# EQBasePCB_V_1_0.net
KiCad netlist of a schematic drawn in EAGLE
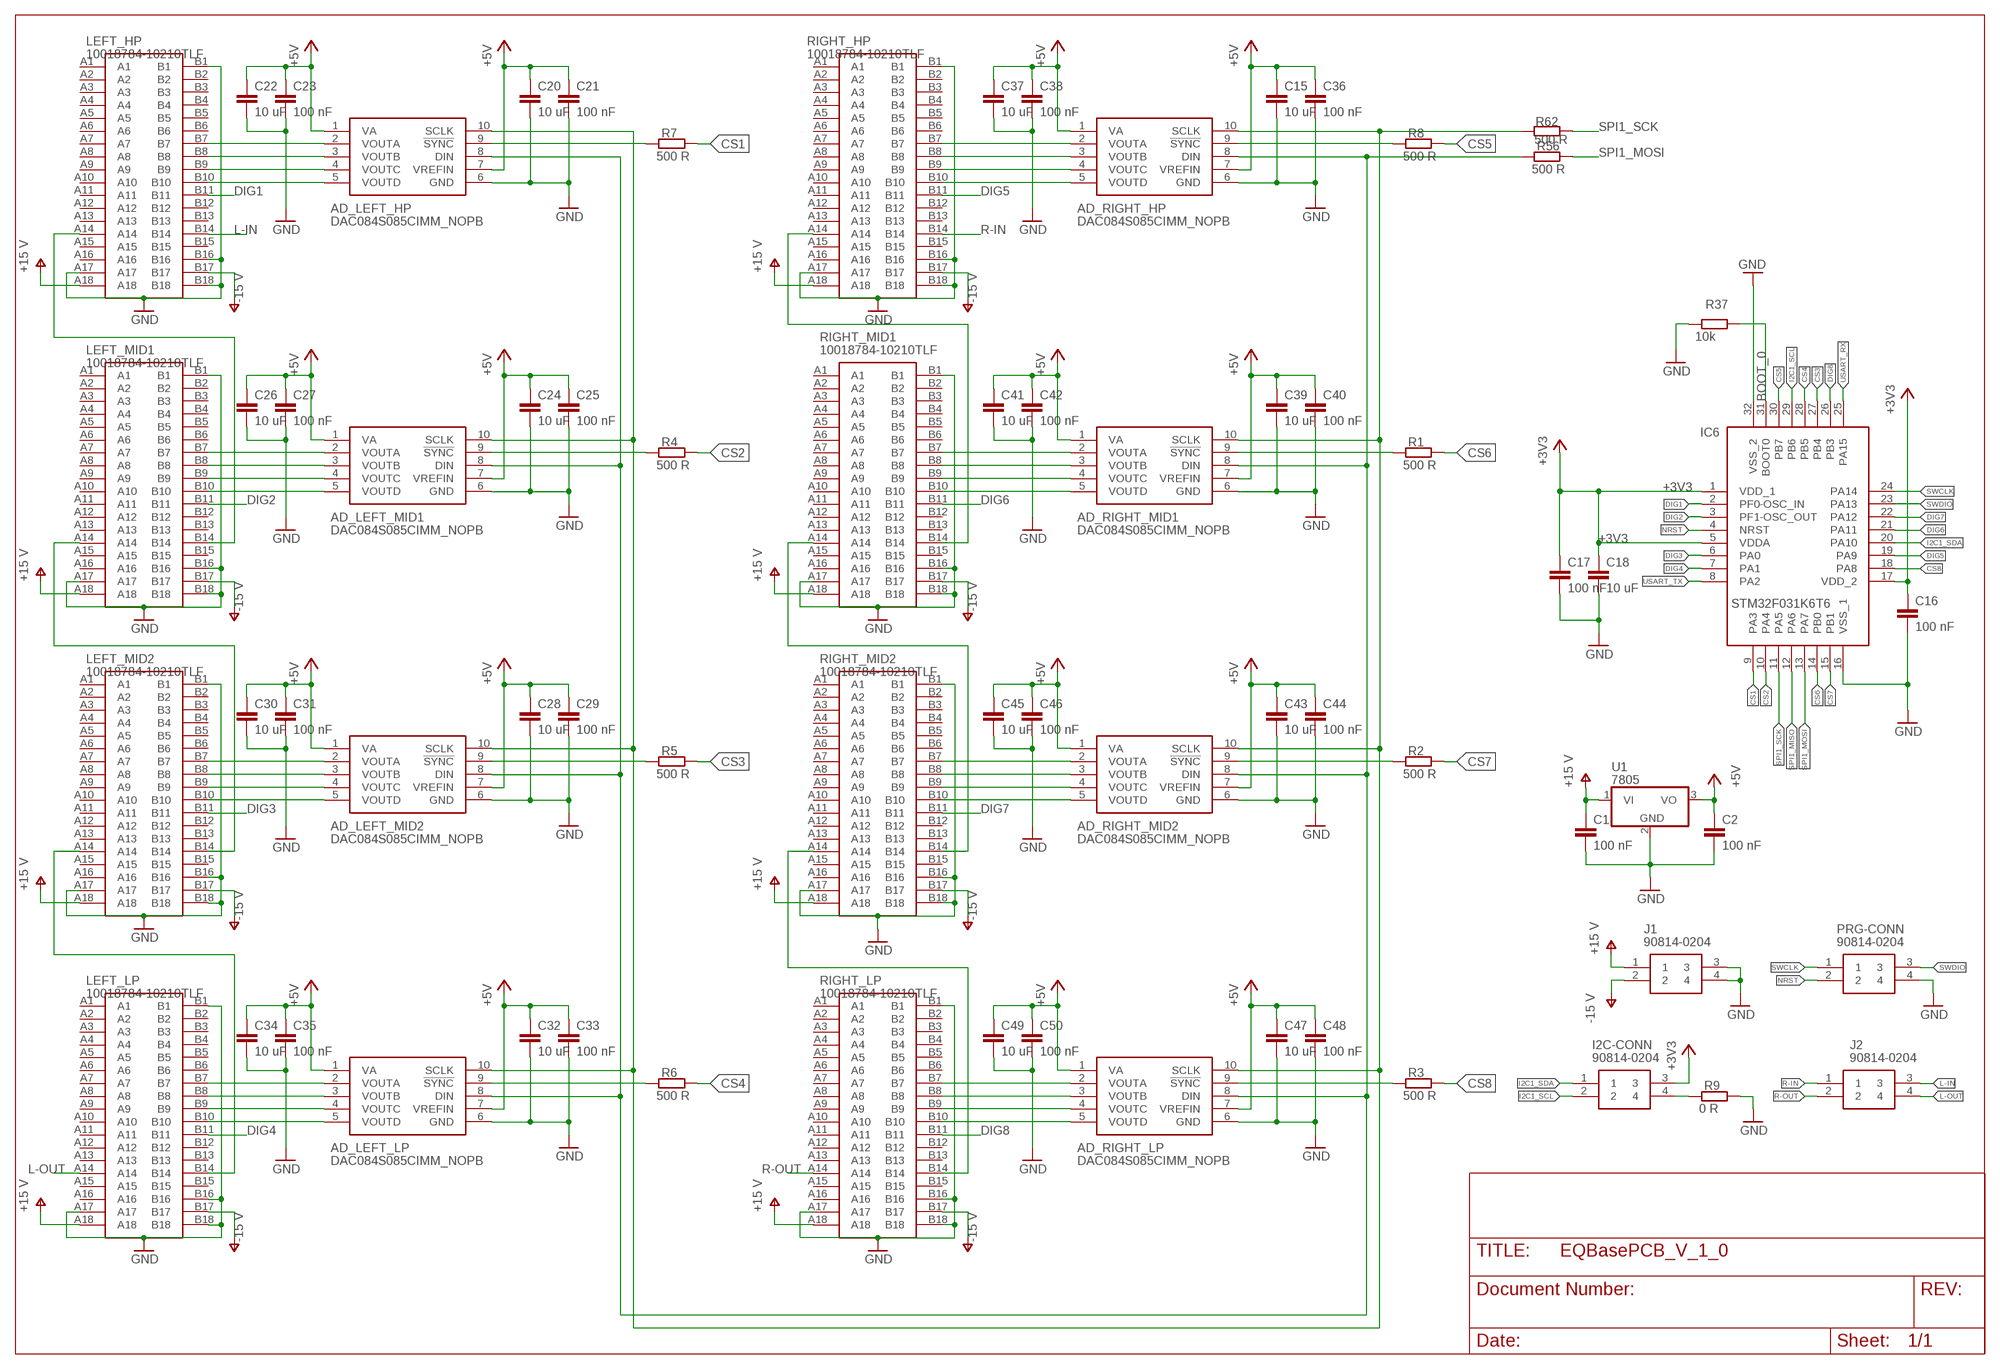
[diagram p0: schematic, sheet 1]

(export (version "E")
  (design (tool "Eeschema 10.0.6"))
  (components
    (comp (ref "AD_LEFT_HP")
      (value "DAC084S085CIMM_NOPB")
      (footprint "eagle-import:SOP50P490X110-10N")
      (fields (field (name "MOUSER_PART_NUMBER") "926-DAC084S085CIMMNO"))
      (libsource (lib "eagle-import") (part "DAC084S085CIMM_NOPB"))
    )
    (comp (ref "AD_LEFT_LP")
      (value "DAC084S085CIMM_NOPB")
      (footprint "eagle-import:SOP50P490X110-10N")
      (fields (field (name "MOUSER_PART_NUMBER") "926-DAC084S085CIMMNO"))
      (libsource (lib "eagle-import") (part "DAC084S085CIMM_NOPB"))
    )
    (comp (ref "AD_LEFT_MID1")
      (value "DAC084S085CIMM_NOPB")
      (footprint "eagle-import:SOP50P490X110-10N")
      (fields (field (name "MOUSER_PART_NUMBER") "926-DAC084S085CIMMNO"))
      (libsource (lib "eagle-import") (part "DAC084S085CIMM_NOPB"))
    )
    (comp (ref "AD_LEFT_MID2")
      (value "DAC084S085CIMM_NOPB")
      (footprint "eagle-import:SOP50P490X110-10N")
      (fields (field (name "MOUSER_PART_NUMBER") "926-DAC084S085CIMMNO"))
      (libsource (lib "eagle-import") (part "DAC084S085CIMM_NOPB"))
    )
    (comp (ref "AD_RIGHT_HP")
      (value "DAC084S085CIMM_NOPB")
      (footprint "eagle-import:SOP50P490X110-10N")
      (fields (field (name "MOUSER_PART_NUMBER") "926-DAC084S085CIMMNO"))
      (libsource (lib "eagle-import") (part "DAC084S085CIMM_NOPB"))
    )
    (comp (ref "AD_RIGHT_LP")
      (value "DAC084S085CIMM_NOPB")
      (footprint "eagle-import:SOP50P490X110-10N")
      (fields (field (name "MOUSER_PART_NUMBER") "926-DAC084S085CIMMNO"))
      (libsource (lib "eagle-import") (part "DAC084S085CIMM_NOPB"))
    )
    (comp (ref "AD_RIGHT_MID1")
      (value "DAC084S085CIMM_NOPB")
      (footprint "eagle-import:SOP50P490X110-10N")
      (fields (field (name "MOUSER_PART_NUMBER") "926-DAC084S085CIMMNO"))
      (libsource (lib "eagle-import") (part "DAC084S085CIMM_NOPB"))
    )
    (comp (ref "AD_RIGHT_MID2")
      (value "DAC084S085CIMM_NOPB")
      (footprint "eagle-import:SOP50P490X110-10N")
      (fields (field (name "MOUSER_PART_NUMBER") "926-DAC084S085CIMMNO"))
      (libsource (lib "eagle-import") (part "DAC084S085CIMM_NOPB"))
    )
    (comp (ref "C1")
      (value "100 nF")
      (footprint "eagle-import:C0603")
      (libsource (lib "eagle-import") (part "CAPACITOR_0603"))
    )
    (comp (ref "C2")
      (value "100 nF")
      (footprint "eagle-import:C0603")
      (libsource (lib "eagle-import") (part "CAPACITOR_0603"))
    )
    (comp (ref "C15")
      (value "10 uF")
      (footprint "eagle-import:C1206")
      (libsource (lib "eagle-import") (part "CAPACITOR_1206"))
    )
    (comp (ref "C16")
      (value "100 nF")
      (footprint "eagle-import:C0603")
      (libsource (lib "eagle-import") (part "CAPACITOR_0603"))
    )
    (comp (ref "C17")
      (value "100 nF")
      (footprint "eagle-import:C0603")
      (libsource (lib "eagle-import") (part "CAPACITOR_0603"))
    )
    (comp (ref "C18")
      (value "10 uF")
      (footprint "eagle-import:C1206")
      (libsource (lib "eagle-import") (part "CAPACITOR_1206"))
    )
    (comp (ref "C20")
      (value "10 uF")
      (footprint "eagle-import:C1206")
      (libsource (lib "eagle-import") (part "CAPACITOR_1206"))
    )
    (comp (ref "C21")
      (value "100 nF")
      (footprint "eagle-import:C0603")
      (libsource (lib "eagle-import") (part "CAPACITOR_0603"))
    )
    (comp (ref "C22")
      (value "10 uF")
      (footprint "eagle-import:C1206")
      (libsource (lib "eagle-import") (part "CAPACITOR_1206"))
    )
    (comp (ref "C23")
      (value "100 nF")
      (footprint "eagle-import:C0603")
      (libsource (lib "eagle-import") (part "CAPACITOR_0603"))
    )
    (comp (ref "C24")
      (value "10 uF")
      (footprint "eagle-import:C1206")
      (libsource (lib "eagle-import") (part "CAPACITOR_1206"))
    )
    (comp (ref "C25")
      (value "100 nF")
      (footprint "eagle-import:C0603")
      (libsource (lib "eagle-import") (part "CAPACITOR_0603"))
    )
    (comp (ref "C26")
      (value "10 uF")
      (footprint "eagle-import:C1206")
      (libsource (lib "eagle-import") (part "CAPACITOR_1206"))
    )
    (comp (ref "C27")
      (value "100 nF")
      (footprint "eagle-import:C0603")
      (libsource (lib "eagle-import") (part "CAPACITOR_0603"))
    )
    (comp (ref "C28")
      (value "10 uF")
      (footprint "eagle-import:C1206")
      (libsource (lib "eagle-import") (part "CAPACITOR_1206"))
    )
    (comp (ref "C29")
      (value "100 nF")
      (footprint "eagle-import:C0603")
      (libsource (lib "eagle-import") (part "CAPACITOR_0603"))
    )
    (comp (ref "C30")
      (value "10 uF")
      (footprint "eagle-import:C1206")
      (libsource (lib "eagle-import") (part "CAPACITOR_1206"))
    )
    (comp (ref "C31")
      (value "100 nF")
      (footprint "eagle-import:C0603")
      (libsource (lib "eagle-import") (part "CAPACITOR_0603"))
    )
    (comp (ref "C32")
      (value "10 uF")
      (footprint "eagle-import:C1206")
      (libsource (lib "eagle-import") (part "CAPACITOR_1206"))
    )
    (comp (ref "C33")
      (value "100 nF")
      (footprint "eagle-import:C0603")
      (libsource (lib "eagle-import") (part "CAPACITOR_0603"))
    )
    (comp (ref "C34")
      (value "10 uF")
      (footprint "eagle-import:C1206")
      (libsource (lib "eagle-import") (part "CAPACITOR_1206"))
    )
    (comp (ref "C35")
      (value "100 nF")
      (footprint "eagle-import:C0603")
      (libsource (lib "eagle-import") (part "CAPACITOR_0603"))
    )
    (comp (ref "C36")
      (value "100 nF")
      (footprint "eagle-import:C0603")
      (libsource (lib "eagle-import") (part "CAPACITOR_0603"))
    )
    (comp (ref "C37")
      (value "10 uF")
      (footprint "eagle-import:C1206")
      (libsource (lib "eagle-import") (part "CAPACITOR_1206"))
    )
    (comp (ref "C38")
      (value "100 nF")
      (footprint "eagle-import:C0603")
      (libsource (lib "eagle-import") (part "CAPACITOR_0603"))
    )
    (comp (ref "C39")
      (value "10 uF")
      (footprint "eagle-import:C1206")
      (libsource (lib "eagle-import") (part "CAPACITOR_1206"))
    )
    (comp (ref "C40")
      (value "100 nF")
      (footprint "eagle-import:C0603")
      (libsource (lib "eagle-import") (part "CAPACITOR_0603"))
    )
    (comp (ref "C41")
      (value "10 uF")
      (footprint "eagle-import:C1206")
      (libsource (lib "eagle-import") (part "CAPACITOR_1206"))
    )
    (comp (ref "C42")
      (value "100 nF")
      (footprint "eagle-import:C0603")
      (libsource (lib "eagle-import") (part "CAPACITOR_0603"))
    )
    (comp (ref "C43")
      (value "10 uF")
      (footprint "eagle-import:C1206")
      (libsource (lib "eagle-import") (part "CAPACITOR_1206"))
    )
    (comp (ref "C44")
      (value "100 nF")
      (footprint "eagle-import:C0603")
      (libsource (lib "eagle-import") (part "CAPACITOR_0603"))
    )
    (comp (ref "C45")
      (value "10 uF")
      (footprint "eagle-import:C1206")
      (libsource (lib "eagle-import") (part "CAPACITOR_1206"))
    )
    (comp (ref "C46")
      (value "100 nF")
      (footprint "eagle-import:C0603")
      (libsource (lib "eagle-import") (part "CAPACITOR_0603"))
    )
    (comp (ref "C47")
      (value "10 uF")
      (footprint "eagle-import:C1206")
      (libsource (lib "eagle-import") (part "CAPACITOR_1206"))
    )
    (comp (ref "C48")
      (value "100 nF")
      (footprint "eagle-import:C0603")
      (libsource (lib "eagle-import") (part "CAPACITOR_0603"))
    )
    (comp (ref "C49")
      (value "10 uF")
      (footprint "eagle-import:C1206")
      (libsource (lib "eagle-import") (part "CAPACITOR_1206"))
    )
    (comp (ref "C50")
      (value "100 nF")
      (footprint "eagle-import:C0603")
      (libsource (lib "eagle-import") (part "CAPACITOR_0603"))
    )
    (comp (ref "I2C-CONN")
      (value "90814-0204")
      (footprint "eagle-import:MOLEX_90814-0204")
      (fields (field (name "MOUSER_PART_NUMBER") "538-90814-0204"))
      (libsource (lib "eagle-import") (part "90814-0204"))
    )
    (comp (ref "IC6")
      (value "STM32F031K6T6")
      (footprint "eagle-import:QFP80P900X900X160-32N")
      (fields (field (name "MOUSER_PART_NUMBER") "511-STM32F031K6T6"))
      (libsource (lib "eagle-import") (part "STM32F031K6T6"))
    )
    (comp (ref "J1")
      (value "90814-0204")
      (footprint "eagle-import:MOLEX_90814-0204")
      (fields (field (name "MOUSER_PART_NUMBER") "538-90814-0204"))
      (libsource (lib "eagle-import") (part "90814-0204"))
    )
    (comp (ref "J2")
      (value "90814-0204")
      (footprint "eagle-import:MOLEX_90814-0204")
      (fields (field (name "MOUSER_PART_NUMBER") "538-90814-0204"))
      (libsource (lib "eagle-import") (part "90814-0204"))
    )
    (comp (ref "LEFT_HP")
      (value "10018784-10210TLF")
      (footprint "eagle-import:1001878410210TLF")
      (fields (field (name "MOUSER_PART_NUMBER") "649-1001878410210TLF"))
      (libsource (lib "eagle-import") (part "10018784-10210TLF"))
    )
    (comp (ref "LEFT_LP")
      (value "10018784-10210TLF")
      (footprint "eagle-import:1001878410210TLF")
      (fields (field (name "MOUSER_PART_NUMBER") "649-1001878410210TLF"))
      (libsource (lib "eagle-import") (part "10018784-10210TLF"))
    )
    (comp (ref "LEFT_MID1")
      (value "10018784-10210TLF")
      (footprint "eagle-import:1001878410210TLF")
      (fields (field (name "MOUSER_PART_NUMBER") "649-1001878410210TLF"))
      (libsource (lib "eagle-import") (part "10018784-10210TLF"))
    )
    (comp (ref "LEFT_MID2")
      (value "10018784-10210TLF")
      (footprint "eagle-import:1001878410210TLF")
      (fields (field (name "MOUSER_PART_NUMBER") "649-1001878410210TLF"))
      (libsource (lib "eagle-import") (part "10018784-10210TLF"))
    )
    (comp (ref "PRG-CONN")
      (value "90814-0204")
      (footprint "eagle-import:MOLEX_90814-0204")
      (fields (field (name "MOUSER_PART_NUMBER") "538-90814-0204"))
      (libsource (lib "eagle-import") (part "90814-0204"))
    )
    (comp (ref "R1")
      (value "500 R")
      (footprint "eagle-import:R0603")
      (libsource (lib "eagle-import") (part "RESISTOR_0603"))
    )
    (comp (ref "R2")
      (value "500 R")
      (footprint "eagle-import:R0603")
      (libsource (lib "eagle-import") (part "RESISTOR_0603"))
    )
    (comp (ref "R3")
      (value "500 R")
      (footprint "eagle-import:R0603")
      (libsource (lib "eagle-import") (part "RESISTOR_0603"))
    )
    (comp (ref "R4")
      (value "500 R")
      (footprint "eagle-import:R0603")
      (libsource (lib "eagle-import") (part "RESISTOR_0603"))
    )
    (comp (ref "R5")
      (value "500 R")
      (footprint "eagle-import:R0603")
      (libsource (lib "eagle-import") (part "RESISTOR_0603"))
    )
    (comp (ref "R6")
      (value "500 R")
      (footprint "eagle-import:R0603")
      (libsource (lib "eagle-import") (part "RESISTOR_0603"))
    )
    (comp (ref "R7")
      (value "500 R")
      (footprint "eagle-import:R0603")
      (libsource (lib "eagle-import") (part "RESISTOR_0603"))
    )
    (comp (ref "R8")
      (value "500 R")
      (footprint "eagle-import:R0603")
      (libsource (lib "eagle-import") (part "RESISTOR_0603"))
    )
    (comp (ref "R9")
      (value "0 R")
      (footprint "eagle-import:R0603")
      (libsource (lib "eagle-import") (part "RESISTOR_0603"))
    )
    (comp (ref "R37")
      (value "10k")
      (footprint "eagle-import:R0603")
      (libsource (lib "eagle-import") (part "RESISTOR_0603"))
    )
    (comp (ref "R56")
      (value "500 R")
      (footprint "eagle-import:R0603")
      (libsource (lib "eagle-import") (part "RESISTOR_0603"))
    )
    (comp (ref "R62")
      (value "500 R")
      (footprint "eagle-import:R0603")
      (libsource (lib "eagle-import") (part "RESISTOR_0603"))
    )
    (comp (ref "RIGHT_HP")
      (value "10018784-10210TLF")
      (footprint "eagle-import:1001878410210TLF")
      (fields (field (name "MOUSER_PART_NUMBER") "649-1001878410210TLF"))
      (libsource (lib "eagle-import") (part "10018784-10210TLF"))
    )
    (comp (ref "RIGHT_LP")
      (value "10018784-10210TLF")
      (footprint "eagle-import:1001878410210TLF")
      (fields (field (name "MOUSER_PART_NUMBER") "649-1001878410210TLF"))
      (libsource (lib "eagle-import") (part "10018784-10210TLF"))
    )
    (comp (ref "RIGHT_MID1")
      (value "10018784-10210TLF")
      (footprint "eagle-import:1001878410210TLF")
      (fields (field (name "MOUSER_PART_NUMBER") "649-1001878410210TLF"))
      (libsource (lib "eagle-import") (part "10018784-10210TLF"))
    )
    (comp (ref "RIGHT_MID2")
      (value "10018784-10210TLF")
      (footprint "eagle-import:1001878410210TLF")
      (fields (field (name "MOUSER_PART_NUMBER") "649-1001878410210TLF"))
      (libsource (lib "eagle-import") (part "10018784-10210TLF"))
    )
    (comp (ref "U1")
      (value "7805")
      (footprint "eagle-import:TO252")
      (libsource (lib "eagle-import") (part "78_SMD"))
    )
  )
  (nets
    (net (code "1") (name "+3V3") (class "Default")
      (node (ref "C16") (pin "1") (pinfunction "1_1") (pintype "passive"))
      (node (ref "C17") (pin "1") (pinfunction "1_1") (pintype "passive"))
      (node (ref "C18") (pin "1") (pinfunction "1_1") (pintype "passive"))
      (node (ref "I2C-CONN") (pin "3") (pinfunction "3_3") (pintype "bidirectional"))
      (node (ref "IC6") (pin "1") (pinfunction "VDD_1_1") (pintype "bidirectional"))
      (node (ref "IC6") (pin "17") (pinfunction "VDD_2_17") (pintype "bidirectional"))
      (node (ref "IC6") (pin "5") (pinfunction "VDDA_5") (pintype "bidirectional"))
    )
    (net (code "2") (name "+5V") (class "Default")
      (node (ref "AD_LEFT_HP") (pin "1") (pinfunction "VA_1") (pintype "bidirectional"))
      (node (ref "AD_LEFT_HP") (pin "7") (pinfunction "VREFIN_7") (pintype "bidirectional"))
      (node (ref "AD_LEFT_LP") (pin "1") (pinfunction "VA_1") (pintype "bidirectional"))
      (node (ref "AD_LEFT_LP") (pin "7") (pinfunction "VREFIN_7") (pintype "bidirectional"))
      (node (ref "AD_LEFT_MID1") (pin "1") (pinfunction "VA_1") (pintype "bidirectional"))
      (node (ref "AD_LEFT_MID1") (pin "7") (pinfunction "VREFIN_7") (pintype "bidirectional"))
      (node (ref "AD_LEFT_MID2") (pin "1") (pinfunction "VA_1") (pintype "bidirectional"))
      (node (ref "AD_LEFT_MID2") (pin "7") (pinfunction "VREFIN_7") (pintype "bidirectional"))
      (node (ref "AD_RIGHT_HP") (pin "1") (pinfunction "VA_1") (pintype "bidirectional"))
      (node (ref "AD_RIGHT_HP") (pin "7") (pinfunction "VREFIN_7") (pintype "bidirectional"))
      (node (ref "AD_RIGHT_LP") (pin "1") (pinfunction "VA_1") (pintype "bidirectional"))
      (node (ref "AD_RIGHT_LP") (pin "7") (pinfunction "VREFIN_7") (pintype "bidirectional"))
      (node (ref "AD_RIGHT_MID1") (pin "1") (pinfunction "VA_1") (pintype "bidirectional"))
      (node (ref "AD_RIGHT_MID1") (pin "7") (pinfunction "VREFIN_7") (pintype "bidirectional"))
      (node (ref "AD_RIGHT_MID2") (pin "1") (pinfunction "VA_1") (pintype "bidirectional"))
      (node (ref "AD_RIGHT_MID2") (pin "7") (pinfunction "VREFIN_7") (pintype "bidirectional"))
      (node (ref "C15") (pin "1") (pinfunction "1_1") (pintype "passive"))
      (node (ref "C2") (pin "1") (pinfunction "1_1") (pintype "passive"))
      (node (ref "C20") (pin "1") (pinfunction "1_1") (pintype "passive"))
      (node (ref "C21") (pin "1") (pinfunction "1_1") (pintype "passive"))
      (node (ref "C22") (pin "1") (pinfunction "1_1") (pintype "passive"))
      (node (ref "C23") (pin "1") (pinfunction "1_1") (pintype "passive"))
      (node (ref "C24") (pin "1") (pinfunction "1_1") (pintype "passive"))
      (node (ref "C25") (pin "1") (pinfunction "1_1") (pintype "passive"))
      (node (ref "C26") (pin "1") (pinfunction "1_1") (pintype "passive"))
      (node (ref "C27") (pin "1") (pinfunction "1_1") (pintype "passive"))
      (node (ref "C28") (pin "1") (pinfunction "1_1") (pintype "passive"))
      (node (ref "C29") (pin "1") (pinfunction "1_1") (pintype "passive"))
      (node (ref "C30") (pin "1") (pinfunction "1_1") (pintype "passive"))
      (node (ref "C31") (pin "1") (pinfunction "1_1") (pintype "passive"))
      (node (ref "C32") (pin "1") (pinfunction "1_1") (pintype "passive"))
      (node (ref "C33") (pin "1") (pinfunction "1_1") (pintype "passive"))
      (node (ref "C34") (pin "1") (pinfunction "1_1") (pintype "passive"))
      (node (ref "C35") (pin "1") (pinfunction "1_1") (pintype "passive"))
      (node (ref "C36") (pin "1") (pinfunction "1_1") (pintype "passive"))
      (node (ref "C37") (pin "1") (pinfunction "1_1") (pintype "passive"))
      (node (ref "C38") (pin "1") (pinfunction "1_1") (pintype "passive"))
      (node (ref "C39") (pin "1") (pinfunction "1_1") (pintype "passive"))
      (node (ref "C40") (pin "1") (pinfunction "1_1") (pintype "passive"))
      (node (ref "C41") (pin "1") (pinfunction "1_1") (pintype "passive"))
      (node (ref "C42") (pin "1") (pinfunction "1_1") (pintype "passive"))
      (node (ref "C43") (pin "1") (pinfunction "1_1") (pintype "passive"))
      (node (ref "C44") (pin "1") (pinfunction "1_1") (pintype "passive"))
      (node (ref "C45") (pin "1") (pinfunction "1_1") (pintype "passive"))
      (node (ref "C46") (pin "1") (pinfunction "1_1") (pintype "passive"))
      (node (ref "C47") (pin "1") (pinfunction "1_1") (pintype "passive"))
      (node (ref "C48") (pin "1") (pinfunction "1_1") (pintype "passive"))
      (node (ref "C49") (pin "1") (pinfunction "1_1") (pintype "passive"))
      (node (ref "C50") (pin "1") (pinfunction "1_1") (pintype "passive"))
      (node (ref "U1") (pin "3") (pinfunction "VO_3") (pintype "passive"))
    )
    (net (code "3") (name "+15 V") (class "Default")
      (node (ref "C1") (pin "1") (pinfunction "1_1") (pintype "passive"))
      (node (ref "J1") (pin "1") (pinfunction "1_1") (pintype "bidirectional"))
      (node (ref "LEFT_HP") (pin "A18") (pinfunction "A18_A18") (pintype "bidirectional"))
      (node (ref "LEFT_LP") (pin "A18") (pinfunction "A18_A18") (pintype "bidirectional"))
      (node (ref "LEFT_MID1") (pin "A18") (pinfunction "A18_A18") (pintype "bidirectional"))
      (node (ref "LEFT_MID2") (pin "A18") (pinfunction "A18_A18") (pintype "bidirectional"))
      (node (ref "RIGHT_HP") (pin "A18") (pinfunction "A18_A18") (pintype "bidirectional"))
      (node (ref "RIGHT_LP") (pin "A18") (pinfunction "A18_A18") (pintype "bidirectional"))
      (node (ref "RIGHT_MID1") (pin "A18") (pinfunction "A18_A18") (pintype "bidirectional"))
      (node (ref "RIGHT_MID2") (pin "A18") (pinfunction "A18_A18") (pintype "bidirectional"))
      (node (ref "U1") (pin "1") (pinfunction "VI_1") (pintype "input"))
    )
    (net (code "4") (name "-15 V") (class "Default")
      (node (ref "J1") (pin "2") (pinfunction "2_2") (pintype "bidirectional"))
      (node (ref "LEFT_HP") (pin "B17") (pinfunction "B17_B17") (pintype "bidirectional"))
      (node (ref "LEFT_LP") (pin "B17") (pinfunction "B17_B17") (pintype "bidirectional"))
      (node (ref "LEFT_MID1") (pin "B17") (pinfunction "B17_B17") (pintype "bidirectional"))
      (node (ref "LEFT_MID2") (pin "B17") (pinfunction "B17_B17") (pintype "bidirectional"))
      (node (ref "RIGHT_HP") (pin "B17") (pinfunction "B17_B17") (pintype "bidirectional"))
      (node (ref "RIGHT_LP") (pin "B17") (pinfunction "B17_B17") (pintype "bidirectional"))
      (node (ref "RIGHT_MID1") (pin "B17") (pinfunction "B17_B17") (pintype "bidirectional"))
      (node (ref "RIGHT_MID2") (pin "B17") (pinfunction "B17_B17") (pintype "bidirectional"))
    )
    (net (code "5") (name "/BOOT_0") (class "Default")
      (node (ref "IC6") (pin "31") (pinfunction "BOOT0_31") (pintype "bidirectional"))
      (node (ref "R37") (pin "2") (pinfunction "2_2") (pintype "passive"))
    )
    (net (code "6") (name "CS1") (class "Default")
      (node (ref "IC6") (pin "9") (pinfunction "PA3_9") (pintype "bidirectional"))
      (node (ref "R7") (pin "2") (pinfunction "2_2") (pintype "passive"))
    )
    (net (code "7") (name "CS2") (class "Default")
      (node (ref "IC6") (pin "10") (pinfunction "PA4_10") (pintype "bidirectional"))
      (node (ref "R4") (pin "2") (pinfunction "2_2") (pintype "passive"))
    )
    (net (code "8") (name "CS3") (class "Default")
      (node (ref "IC6") (pin "27") (pinfunction "PB4_27") (pintype "bidirectional"))
      (node (ref "R5") (pin "2") (pinfunction "2_2") (pintype "passive"))
    )
    (net (code "9") (name "CS4") (class "Default")
      (node (ref "IC6") (pin "28") (pinfunction "PB5_28") (pintype "bidirectional"))
      (node (ref "R6") (pin "2") (pinfunction "2_2") (pintype "passive"))
    )
    (net (code "10") (name "CS5") (class "Default")
      (node (ref "IC6") (pin "30") (pinfunction "PB7_30") (pintype "bidirectional"))
      (node (ref "R8") (pin "2") (pinfunction "2_2") (pintype "passive"))
    )
    (net (code "11") (name "CS6") (class "Default")
      (node (ref "IC6") (pin "14") (pinfunction "PB0_14") (pintype "bidirectional"))
      (node (ref "R1") (pin "2") (pinfunction "2_2") (pintype "passive"))
    )
    (net (code "12") (name "CS7") (class "Default")
      (node (ref "IC6") (pin "15") (pinfunction "PB1_15") (pintype "bidirectional"))
      (node (ref "R2") (pin "2") (pinfunction "2_2") (pintype "passive"))
    )
    (net (code "13") (name "CS8") (class "Default")
      (node (ref "IC6") (pin "18") (pinfunction "PA8_18") (pintype "bidirectional"))
      (node (ref "R3") (pin "2") (pinfunction "2_2") (pintype "passive"))
    )
    (net (code "14") (name "DIG1") (class "Default")
      (node (ref "IC6") (pin "2") (pinfunction "PF0-OSC_IN_2") (pintype "bidirectional"))
      (node (ref "LEFT_HP") (pin "B11") (pinfunction "B11_B11") (pintype "bidirectional"))
    )
    (net (code "15") (name "DIG2") (class "Default")
      (node (ref "IC6") (pin "3") (pinfunction "PF1-OSC_OUT_3") (pintype "bidirectional"))
      (node (ref "LEFT_MID1") (pin "B11") (pinfunction "B11_B11") (pintype "bidirectional"))
    )
    (net (code "16") (name "DIG3") (class "Default")
      (node (ref "IC6") (pin "6") (pinfunction "PA0_6") (pintype "bidirectional"))
      (node (ref "LEFT_MID2") (pin "B11") (pinfunction "B11_B11") (pintype "bidirectional"))
    )
    (net (code "17") (name "DIG4") (class "Default")
      (node (ref "IC6") (pin "7") (pinfunction "PA1_7") (pintype "bidirectional"))
      (node (ref "LEFT_LP") (pin "B11") (pinfunction "B11_B11") (pintype "bidirectional"))
    )
    (net (code "18") (name "DIG5") (class "Default")
      (node (ref "IC6") (pin "19") (pinfunction "PA9_19") (pintype "bidirectional"))
      (node (ref "RIGHT_HP") (pin "B11") (pinfunction "B11_B11") (pintype "bidirectional"))
    )
    (net (code "19") (name "DIG6") (class "Default")
      (node (ref "IC6") (pin "21") (pinfunction "PA11_21") (pintype "bidirectional"))
      (node (ref "RIGHT_MID1") (pin "B11") (pinfunction "B11_B11") (pintype "bidirectional"))
    )
    (net (code "20") (name "DIG7") (class "Default")
      (node (ref "IC6") (pin "22") (pinfunction "PA12_22") (pintype "bidirectional"))
      (node (ref "RIGHT_MID2") (pin "B11") (pinfunction "B11_B11") (pintype "bidirectional"))
    )
    (net (code "21") (name "DIG8") (class "Default")
      (node (ref "IC6") (pin "26") (pinfunction "PB3_26") (pintype "bidirectional"))
      (node (ref "RIGHT_LP") (pin "B11") (pinfunction "B11_B11") (pintype "bidirectional"))
    )
    (net (code "22") (name "GND") (class "Default")
      (node (ref "AD_LEFT_HP") (pin "6") (pinfunction "GND_6") (pintype "bidirectional"))
      (node (ref "AD_LEFT_LP") (pin "6") (pinfunction "GND_6") (pintype "bidirectional"))
      (node (ref "AD_LEFT_MID1") (pin "6") (pinfunction "GND_6") (pintype "bidirectional"))
      (node (ref "AD_LEFT_MID2") (pin "6") (pinfunction "GND_6") (pintype "bidirectional"))
      (node (ref "AD_RIGHT_HP") (pin "6") (pinfunction "GND_6") (pintype "bidirectional"))
      (node (ref "AD_RIGHT_LP") (pin "6") (pinfunction "GND_6") (pintype "bidirectional"))
      (node (ref "AD_RIGHT_MID1") (pin "6") (pinfunction "GND_6") (pintype "bidirectional"))
      (node (ref "AD_RIGHT_MID2") (pin "6") (pinfunction "GND_6") (pintype "bidirectional"))
      (node (ref "C1") (pin "2") (pinfunction "2_2") (pintype "passive"))
      (node (ref "C15") (pin "2") (pinfunction "2_2") (pintype "passive"))
      (node (ref "C16") (pin "2") (pinfunction "2_2") (pintype "passive"))
      (node (ref "C17") (pin "2") (pinfunction "2_2") (pintype "passive"))
      (node (ref "C18") (pin "2") (pinfunction "2_2") (pintype "passive"))
      (node (ref "C2") (pin "2") (pinfunction "2_2") (pintype "passive"))
      (node (ref "C20") (pin "2") (pinfunction "2_2") (pintype "passive"))
      (node (ref "C21") (pin "2") (pinfunction "2_2") (pintype "passive"))
      (node (ref "C22") (pin "2") (pinfunction "2_2") (pintype "passive"))
      (node (ref "C23") (pin "2") (pinfunction "2_2") (pintype "passive"))
      (node (ref "C24") (pin "2") (pinfunction "2_2") (pintype "passive"))
      (node (ref "C25") (pin "2") (pinfunction "2_2") (pintype "passive"))
      (node (ref "C26") (pin "2") (pinfunction "2_2") (pintype "passive"))
      (node (ref "C27") (pin "2") (pinfunction "2_2") (pintype "passive"))
      (node (ref "C28") (pin "2") (pinfunction "2_2") (pintype "passive"))
      (node (ref "C29") (pin "2") (pinfunction "2_2") (pintype "passive"))
      (node (ref "C30") (pin "2") (pinfunction "2_2") (pintype "passive"))
      (node (ref "C31") (pin "2") (pinfunction "2_2") (pintype "passive"))
      (node (ref "C32") (pin "2") (pinfunction "2_2") (pintype "passive"))
      (node (ref "C33") (pin "2") (pinfunction "2_2") (pintype "passive"))
      (node (ref "C34") (pin "2") (pinfunction "2_2") (pintype "passive"))
      (node (ref "C35") (pin "2") (pinfunction "2_2") (pintype "passive"))
      (node (ref "C36") (pin "2") (pinfunction "2_2") (pintype "passive"))
      (node (ref "C37") (pin "2") (pinfunction "2_2") (pintype "passive"))
      (node (ref "C38") (pin "2") (pinfunction "2_2") (pintype "passive"))
      (node (ref "C39") (pin "2") (pinfunction "2_2") (pintype "passive"))
      (node (ref "C40") (pin "2") (pinfunction "2_2") (pintype "passive"))
      (node (ref "C41") (pin "2") (pinfunction "2_2") (pintype "passive"))
      (node (ref "C42") (pin "2") (pinfunction "2_2") (pintype "passive"))
      (node (ref "C43") (pin "2") (pinfunction "2_2") (pintype "passive"))
      (node (ref "C44") (pin "2") (pinfunction "2_2") (pintype "passive"))
      (node (ref "C45") (pin "2") (pinfunction "2_2") (pintype "passive"))
      (node (ref "C46") (pin "2") (pinfunction "2_2") (pintype "passive"))
      (node (ref "C47") (pin "2") (pinfunction "2_2") (pintype "passive"))
      (node (ref "C48") (pin "2") (pinfunction "2_2") (pintype "passive"))
      (node (ref "C49") (pin "2") (pinfunction "2_2") (pintype "passive"))
      (node (ref "C50") (pin "2") (pinfunction "2_2") (pintype "passive"))
      (node (ref "IC6") (pin "16") (pinfunction "VSS_1_16") (pintype "bidirectional"))
      (node (ref "IC6") (pin "32") (pinfunction "VSS_2_32") (pintype "bidirectional"))
      (node (ref "J1") (pin "3") (pinfunction "3_3") (pintype "bidirectional"))
      (node (ref "J1") (pin "4") (pinfunction "4_4") (pintype "bidirectional"))
      (node (ref "LEFT_HP") (pin "A17") (pinfunction "A17_A17") (pintype "bidirectional"))
      (node (ref "LEFT_HP") (pin "B1") (pinfunction "B1_B1") (pintype "bidirectional"))
      (node (ref "LEFT_HP") (pin "B16") (pinfunction "B16_B16") (pintype "bidirectional"))
      (node (ref "LEFT_HP") (pin "B18") (pinfunction "B18_B18") (pintype "bidirectional"))
      (node (ref "LEFT_LP") (pin "A17") (pinfunction "A17_A17") (pintype "bidirectional"))
      (node (ref "LEFT_LP") (pin "B1") (pinfunction "B1_B1") (pintype "bidirectional"))
      (node (ref "LEFT_LP") (pin "B16") (pinfunction "B16_B16") (pintype "bidirectional"))
      (node (ref "LEFT_LP") (pin "B18") (pinfunction "B18_B18") (pintype "bidirectional"))
      (node (ref "LEFT_MID1") (pin "A17") (pinfunction "A17_A17") (pintype "bidirectional"))
      (node (ref "LEFT_MID1") (pin "B1") (pinfunction "B1_B1") (pintype "bidirectional"))
      (node (ref "LEFT_MID1") (pin "B16") (pinfunction "B16_B16") (pintype "bidirectional"))
      (node (ref "LEFT_MID1") (pin "B18") (pinfunction "B18_B18") (pintype "bidirectional"))
      (node (ref "LEFT_MID2") (pin "A17") (pinfunction "A17_A17") (pintype "bidirectional"))
      (node (ref "LEFT_MID2") (pin "B1") (pinfunction "B1_B1") (pintype "bidirectional"))
      (node (ref "LEFT_MID2") (pin "B16") (pinfunction "B16_B16") (pintype "bidirectional"))
      (node (ref "LEFT_MID2") (pin "B18") (pinfunction "B18_B18") (pintype "bidirectional"))
      (node (ref "PRG-CONN") (pin "4") (pinfunction "4_4") (pintype "bidirectional"))
      (node (ref "R37") (pin "1") (pinfunction "1_1") (pintype "passive"))
      (node (ref "R9") (pin "2") (pinfunction "2_2") (pintype "passive"))
      (node (ref "RIGHT_HP") (pin "A17") (pinfunction "A17_A17") (pintype "bidirectional"))
      (node (ref "RIGHT_HP") (pin "B1") (pinfunction "B1_B1") (pintype "bidirectional"))
      (node (ref "RIGHT_HP") (pin "B16") (pinfunction "B16_B16") (pintype "bidirectional"))
      (node (ref "RIGHT_HP") (pin "B18") (pinfunction "B18_B18") (pintype "bidirectional"))
      (node (ref "RIGHT_LP") (pin "A17") (pinfunction "A17_A17") (pintype "bidirectional"))
      (node (ref "RIGHT_LP") (pin "B1") (pinfunction "B1_B1") (pintype "bidirectional"))
      (node (ref "RIGHT_LP") (pin "B16") (pinfunction "B16_B16") (pintype "bidirectional"))
      (node (ref "RIGHT_LP") (pin "B18") (pinfunction "B18_B18") (pintype "bidirectional"))
      (node (ref "RIGHT_MID1") (pin "A17") (pinfunction "A17_A17") (pintype "bidirectional"))
      (node (ref "RIGHT_MID1") (pin "B1") (pinfunction "B1_B1") (pintype "bidirectional"))
      (node (ref "RIGHT_MID1") (pin "B16") (pinfunction "B16_B16") (pintype "bidirectional"))
      (node (ref "RIGHT_MID1") (pin "B18") (pinfunction "B18_B18") (pintype "bidirectional"))
      (node (ref "RIGHT_MID2") (pin "A17") (pinfunction "A17_A17") (pintype "bidirectional"))
      (node (ref "RIGHT_MID2") (pin "B1") (pinfunction "B1_B1") (pintype "bidirectional"))
      (node (ref "RIGHT_MID2") (pin "B16") (pinfunction "B16_B16") (pintype "bidirectional"))
      (node (ref "RIGHT_MID2") (pin "B18") (pinfunction "B18_B18") (pintype "bidirectional"))
      (node (ref "U1") (pin "2") (pinfunction "GND_2") (pintype "passive"))
    )
    (net (code "23") (name "I2C1_SCL") (class "Default")
      (node (ref "I2C-CONN") (pin "2") (pinfunction "2_2") (pintype "bidirectional"))
      (node (ref "IC6") (pin "29") (pinfunction "PB6_29") (pintype "bidirectional"))
    )
    (net (code "24") (name "I2C1_SDA") (class "Default")
      (node (ref "I2C-CONN") (pin "1") (pinfunction "1_1") (pintype "bidirectional"))
      (node (ref "IC6") (pin "20") (pinfunction "PA10_20") (pintype "bidirectional"))
    )
    (net (code "25") (name "L-IN") (class "Default")
      (node (ref "J2") (pin "3") (pinfunction "3_3") (pintype "bidirectional"))
      (node (ref "LEFT_HP") (pin "B14") (pinfunction "B14_B14") (pintype "bidirectional"))
    )
    (net (code "26") (name "L-OUT") (class "Default")
      (node (ref "J2") (pin "4") (pinfunction "4_4") (pintype "bidirectional"))
      (node (ref "LEFT_LP") (pin "A14") (pinfunction "A14_A14") (pintype "bidirectional"))
    )
    (net (code "27") (name "NRST") (class "Default")
      (node (ref "IC6") (pin "4") (pinfunction "NRST_4") (pintype "bidirectional"))
      (node (ref "PRG-CONN") (pin "2") (pinfunction "2_2") (pintype "bidirectional"))
    )
    (net (code "28") (name "Net-(AD_LEFT_HP-DIN)") (class "Default")
      (node (ref "AD_LEFT_HP") (pin "8") (pinfunction "DIN_8") (pintype "bidirectional"))
      (node (ref "AD_LEFT_LP") (pin "8") (pinfunction "DIN_8") (pintype "bidirectional"))
      (node (ref "AD_LEFT_MID1") (pin "8") (pinfunction "DIN_8") (pintype "bidirectional"))
      (node (ref "AD_LEFT_MID2") (pin "8") (pinfunction "DIN_8") (pintype "bidirectional"))
      (node (ref "AD_RIGHT_HP") (pin "8") (pinfunction "DIN_8") (pintype "bidirectional"))
      (node (ref "AD_RIGHT_LP") (pin "8") (pinfunction "DIN_8") (pintype "bidirectional"))
      (node (ref "AD_RIGHT_MID1") (pin "8") (pinfunction "DIN_8") (pintype "bidirectional"))
      (node (ref "AD_RIGHT_MID2") (pin "8") (pinfunction "DIN_8") (pintype "bidirectional"))
      (node (ref "R56") (pin "1") (pinfunction "1_1") (pintype "passive"))
    )
    (net (code "29") (name "Net-(AD_LEFT_HP-SCLK)") (class "Default")
      (node (ref "AD_LEFT_HP") (pin "10") (pinfunction "SCLK_10") (pintype "bidirectional"))
      (node (ref "AD_LEFT_LP") (pin "10") (pinfunction "SCLK_10") (pintype "bidirectional"))
      (node (ref "AD_LEFT_MID1") (pin "10") (pinfunction "SCLK_10") (pintype "bidirectional"))
      (node (ref "AD_LEFT_MID2") (pin "10") (pinfunction "SCLK_10") (pintype "bidirectional"))
      (node (ref "AD_RIGHT_HP") (pin "10") (pinfunction "SCLK_10") (pintype "bidirectional"))
      (node (ref "AD_RIGHT_LP") (pin "10") (pinfunction "SCLK_10") (pintype "bidirectional"))
      (node (ref "AD_RIGHT_MID1") (pin "10") (pinfunction "SCLK_10") (pintype "bidirectional"))
      (node (ref "AD_RIGHT_MID2") (pin "10") (pinfunction "SCLK_10") (pintype "bidirectional"))
      (node (ref "R62") (pin "1") (pinfunction "1_1") (pintype "passive"))
    )
    (net (code "30") (name "Net-(AD_LEFT_HP-VOUTA)") (class "Default")
      (node (ref "AD_LEFT_HP") (pin "2") (pinfunction "VOUTA_2") (pintype "bidirectional"))
      (node (ref "LEFT_HP") (pin "B7") (pinfunction "B7_B7") (pintype "bidirectional"))
    )
    (net (code "31") (name "Net-(AD_LEFT_HP-VOUTB)") (class "Default")
      (node (ref "AD_LEFT_HP") (pin "3") (pinfunction "VOUTB_3") (pintype "bidirectional"))
      (node (ref "LEFT_HP") (pin "B8") (pinfunction "B8_B8") (pintype "bidirectional"))
    )
    (net (code "32") (name "Net-(AD_LEFT_HP-VOUTC)") (class "Default")
      (node (ref "AD_LEFT_HP") (pin "4") (pinfunction "VOUTC_4") (pintype "bidirectional"))
      (node (ref "LEFT_HP") (pin "B9") (pinfunction "B9_B9") (pintype "bidirectional"))
    )
    (net (code "33") (name "Net-(AD_LEFT_HP-VOUTD)") (class "Default")
      (node (ref "AD_LEFT_HP") (pin "5") (pinfunction "VOUTD_5") (pintype "bidirectional"))
      (node (ref "LEFT_HP") (pin "B10") (pinfunction "B10_B10") (pintype "bidirectional"))
    )
    (net (code "34") (name "Net-(AD_LEFT_HP-~{SYNC})") (class "Default")
      (node (ref "AD_LEFT_HP") (pin "9") (pinfunction "~{SYNC}_9") (pintype "bidirectional"))
      (node (ref "R7") (pin "1") (pinfunction "1_1") (pintype "passive"))
    )
    (net (code "35") (name "Net-(AD_LEFT_LP-VOUTA)") (class "Default")
      (node (ref "AD_LEFT_LP") (pin "2") (pinfunction "VOUTA_2") (pintype "bidirectional"))
      (node (ref "LEFT_LP") (pin "B7") (pinfunction "B7_B7") (pintype "bidirectional"))
    )
    (net (code "36") (name "Net-(AD_LEFT_LP-VOUTB)") (class "Default")
      (node (ref "AD_LEFT_LP") (pin "3") (pinfunction "VOUTB_3") (pintype "bidirectional"))
      (node (ref "LEFT_LP") (pin "B8") (pinfunction "B8_B8") (pintype "bidirectional"))
    )
    (net (code "37") (name "Net-(AD_LEFT_LP-VOUTC)") (class "Default")
      (node (ref "AD_LEFT_LP") (pin "4") (pinfunction "VOUTC_4") (pintype "bidirectional"))
      (node (ref "LEFT_LP") (pin "B9") (pinfunction "B9_B9") (pintype "bidirectional"))
    )
    (net (code "38") (name "Net-(AD_LEFT_LP-VOUTD)") (class "Default")
      (node (ref "AD_LEFT_LP") (pin "5") (pinfunction "VOUTD_5") (pintype "bidirectional"))
      (node (ref "LEFT_LP") (pin "B10") (pinfunction "B10_B10") (pintype "bidirectional"))
    )
    (net (code "39") (name "Net-(AD_LEFT_LP-~{SYNC})") (class "Default")
      (node (ref "AD_LEFT_LP") (pin "9") (pinfunction "~{SYNC}_9") (pintype "bidirectional"))
      (node (ref "R6") (pin "1") (pinfunction "1_1") (pintype "passive"))
    )
    (net (code "40") (name "Net-(AD_LEFT_MID1-VOUTA)") (class "Default")
      (node (ref "AD_LEFT_MID1") (pin "2") (pinfunction "VOUTA_2") (pintype "bidirectional"))
      (node (ref "LEFT_MID1") (pin "B7") (pinfunction "B7_B7") (pintype "bidirectional"))
    )
    (net (code "41") (name "Net-(AD_LEFT_MID1-VOUTB)") (class "Default")
      (node (ref "AD_LEFT_MID1") (pin "3") (pinfunction "VOUTB_3") (pintype "bidirectional"))
      (node (ref "LEFT_MID1") (pin "B8") (pinfunction "B8_B8") (pintype "bidirectional"))
    )
    (net (code "42") (name "Net-(AD_LEFT_MID1-VOUTC)") (class "Default")
      (node (ref "AD_LEFT_MID1") (pin "4") (pinfunction "VOUTC_4") (pintype "bidirectional"))
      (node (ref "LEFT_MID1") (pin "B9") (pinfunction "B9_B9") (pintype "bidirectional"))
    )
    (net (code "43") (name "Net-(AD_LEFT_MID1-VOUTD)") (class "Default")
      (node (ref "AD_LEFT_MID1") (pin "5") (pinfunction "VOUTD_5") (pintype "bidirectional"))
      (node (ref "LEFT_MID1") (pin "B10") (pinfunction "B10_B10") (pintype "bidirectional"))
    )
    (net (code "44") (name "Net-(AD_LEFT_MID1-~{SYNC})") (class "Default")
      (node (ref "AD_LEFT_MID1") (pin "9") (pinfunction "~{SYNC}_9") (pintype "bidirectional"))
      (node (ref "R4") (pin "1") (pinfunction "1_1") (pintype "passive"))
    )
    (net (code "45") (name "Net-(AD_LEFT_MID2-VOUTA)") (class "Default")
      (node (ref "AD_LEFT_MID2") (pin "2") (pinfunction "VOUTA_2") (pintype "bidirectional"))
      (node (ref "LEFT_MID2") (pin "B7") (pinfunction "B7_B7") (pintype "bidirectional"))
    )
    (net (code "46") (name "Net-(AD_LEFT_MID2-VOUTB)") (class "Default")
      (node (ref "AD_LEFT_MID2") (pin "3") (pinfunction "VOUTB_3") (pintype "bidirectional"))
      (node (ref "LEFT_MID2") (pin "B8") (pinfunction "B8_B8") (pintype "bidirectional"))
    )
    (net (code "47") (name "Net-(AD_LEFT_MID2-VOUTC)") (class "Default")
      (node (ref "AD_LEFT_MID2") (pin "4") (pinfunction "VOUTC_4") (pintype "bidirectional"))
      (node (ref "LEFT_MID2") (pin "B9") (pinfunction "B9_B9") (pintype "bidirectional"))
    )
    (net (code "48") (name "Net-(AD_LEFT_MID2-VOUTD)") (class "Default")
      (node (ref "AD_LEFT_MID2") (pin "5") (pinfunction "VOUTD_5") (pintype "bidirectional"))
      (node (ref "LEFT_MID2") (pin "B10") (pinfunction "B10_B10") (pintype "bidirectional"))
    )
    (net (code "49") (name "Net-(AD_LEFT_MID2-~{SYNC})") (class "Default")
      (node (ref "AD_LEFT_MID2") (pin "9") (pinfunction "~{SYNC}_9") (pintype "bidirectional"))
      (node (ref "R5") (pin "1") (pinfunction "1_1") (pintype "passive"))
    )
    (net (code "50") (name "Net-(AD_RIGHT_HP-VOUTA)") (class "Default")
      (node (ref "AD_RIGHT_HP") (pin "2") (pinfunction "VOUTA_2") (pintype "bidirectional"))
      (node (ref "RIGHT_HP") (pin "B7") (pinfunction "B7_B7") (pintype "bidirectional"))
    )
    (net (code "51") (name "Net-(AD_RIGHT_HP-VOUTB)") (class "Default")
      (node (ref "AD_RIGHT_HP") (pin "3") (pinfunction "VOUTB_3") (pintype "bidirectional"))
      (node (ref "RIGHT_HP") (pin "B8") (pinfunction "B8_B8") (pintype "bidirectional"))
    )
    (net (code "52") (name "Net-(AD_RIGHT_HP-VOUTC)") (class "Default")
      (node (ref "AD_RIGHT_HP") (pin "4") (pinfunction "VOUTC_4") (pintype "bidirectional"))
      (node (ref "RIGHT_HP") (pin "B9") (pinfunction "B9_B9") (pintype "bidirectional"))
    )
    (net (code "53") (name "Net-(AD_RIGHT_HP-VOUTD)") (class "Default")
      (node (ref "AD_RIGHT_HP") (pin "5") (pinfunction "VOUTD_5") (pintype "bidirectional"))
      (node (ref "RIGHT_HP") (pin "B10") (pinfunction "B10_B10") (pintype "bidirectional"))
    )
    (net (code "54") (name "Net-(AD_RIGHT_HP-~{SYNC})") (class "Default")
      (node (ref "AD_RIGHT_HP") (pin "9") (pinfunction "~{SYNC}_9") (pintype "bidirectional"))
      (node (ref "R8") (pin "1") (pinfunction "1_1") (pintype "passive"))
    )
    (net (code "55") (name "Net-(AD_RIGHT_LP-VOUTA)") (class "Default")
      (node (ref "AD_RIGHT_LP") (pin "2") (pinfunction "VOUTA_2") (pintype "bidirectional"))
      (node (ref "RIGHT_LP") (pin "B7") (pinfunction "B7_B7") (pintype "bidirectional"))
    )
    (net (code "56") (name "Net-(AD_RIGHT_LP-VOUTB)") (class "Default")
      (node (ref "AD_RIGHT_LP") (pin "3") (pinfunction "VOUTB_3") (pintype "bidirectional"))
      (node (ref "RIGHT_LP") (pin "B8") (pinfunction "B8_B8") (pintype "bidirectional"))
    )
    (net (code "57") (name "Net-(AD_RIGHT_LP-VOUTC)") (class "Default")
      (node (ref "AD_RIGHT_LP") (pin "4") (pinfunction "VOUTC_4") (pintype "bidirectional"))
      (node (ref "RIGHT_LP") (pin "B9") (pinfunction "B9_B9") (pintype "bidirectional"))
    )
    (net (code "58") (name "Net-(AD_RIGHT_LP-VOUTD)") (class "Default")
      (node (ref "AD_RIGHT_LP") (pin "5") (pinfunction "VOUTD_5") (pintype "bidirectional"))
      (node (ref "RIGHT_LP") (pin "B10") (pinfunction "B10_B10") (pintype "bidirectional"))
    )
    (net (code "59") (name "Net-(AD_RIGHT_LP-~{SYNC})") (class "Default")
      (node (ref "AD_RIGHT_LP") (pin "9") (pinfunction "~{SYNC}_9") (pintype "bidirectional"))
      (node (ref "R3") (pin "1") (pinfunction "1_1") (pintype "passive"))
    )
    (net (code "60") (name "Net-(AD_RIGHT_MID1-VOUTA)") (class "Default")
      (node (ref "AD_RIGHT_MID1") (pin "2") (pinfunction "VOUTA_2") (pintype "bidirectional"))
      (node (ref "RIGHT_MID1") (pin "B7") (pinfunction "B7_B7") (pintype "bidirectional"))
    )
    (net (code "61") (name "Net-(AD_RIGHT_MID1-VOUTB)") (class "Default")
      (node (ref "AD_RIGHT_MID1") (pin "3") (pinfunction "VOUTB_3") (pintype "bidirectional"))
      (node (ref "RIGHT_MID1") (pin "B8") (pinfunction "B8_B8") (pintype "bidirectional"))
    )
    (net (code "62") (name "Net-(AD_RIGHT_MID1-VOUTC)") (class "Default")
      (node (ref "AD_RIGHT_MID1") (pin "4") (pinfunction "VOUTC_4") (pintype "bidirectional"))
      (node (ref "RIGHT_MID1") (pin "B9") (pinfunction "B9_B9") (pintype "bidirectional"))
    )
    (net (code "63") (name "Net-(AD_RIGHT_MID1-VOUTD)") (class "Default")
      (node (ref "AD_RIGHT_MID1") (pin "5") (pinfunction "VOUTD_5") (pintype "bidirectional"))
      (node (ref "RIGHT_MID1") (pin "B10") (pinfunction "B10_B10") (pintype "bidirectional"))
    )
    (net (code "64") (name "Net-(AD_RIGHT_MID1-~{SYNC})") (class "Default")
      (node (ref "AD_RIGHT_MID1") (pin "9") (pinfunction "~{SYNC}_9") (pintype "bidirectional"))
      (node (ref "R1") (pin "1") (pinfunction "1_1") (pintype "passive"))
    )
    (net (code "65") (name "Net-(AD_RIGHT_MID2-VOUTA)") (class "Default")
      (node (ref "AD_RIGHT_MID2") (pin "2") (pinfunction "VOUTA_2") (pintype "bidirectional"))
      (node (ref "RIGHT_MID2") (pin "B7") (pinfunction "B7_B7") (pintype "bidirectional"))
    )
    (net (code "66") (name "Net-(AD_RIGHT_MID2-VOUTB)") (class "Default")
      (node (ref "AD_RIGHT_MID2") (pin "3") (pinfunction "VOUTB_3") (pintype "bidirectional"))
      (node (ref "RIGHT_MID2") (pin "B8") (pinfunction "B8_B8") (pintype "bidirectional"))
    )
    (net (code "67") (name "Net-(AD_RIGHT_MID2-VOUTC)") (class "Default")
      (node (ref "AD_RIGHT_MID2") (pin "4") (pinfunction "VOUTC_4") (pintype "bidirectional"))
      (node (ref "RIGHT_MID2") (pin "B9") (pinfunction "B9_B9") (pintype "bidirectional"))
    )
    (net (code "68") (name "Net-(AD_RIGHT_MID2-VOUTD)") (class "Default")
      (node (ref "AD_RIGHT_MID2") (pin "5") (pinfunction "VOUTD_5") (pintype "bidirectional"))
      (node (ref "RIGHT_MID2") (pin "B10") (pinfunction "B10_B10") (pintype "bidirectional"))
    )
    (net (code "69") (name "Net-(AD_RIGHT_MID2-~{SYNC})") (class "Default")
      (node (ref "AD_RIGHT_MID2") (pin "9") (pinfunction "~{SYNC}_9") (pintype "bidirectional"))
      (node (ref "R2") (pin "1") (pinfunction "1_1") (pintype "passive"))
    )
    (net (code "70") (name "Net-(I2C-CONN-Pad4)") (class "Default")
      (node (ref "I2C-CONN") (pin "4") (pinfunction "4_4") (pintype "bidirectional"))
      (node (ref "R9") (pin "1") (pinfunction "1_1") (pintype "passive"))
    )
    (net (code "71") (name "Net-(LEFT_HP-PadA14)") (class "Default")
      (node (ref "LEFT_HP") (pin "A14") (pinfunction "A14_A14") (pintype "bidirectional"))
      (node (ref "LEFT_MID1") (pin "B14") (pinfunction "B14_B14") (pintype "bidirectional"))
    )
    (net (code "72") (name "Net-(LEFT_LP-PadB14)") (class "Default")
      (node (ref "LEFT_LP") (pin "B14") (pinfunction "B14_B14") (pintype "bidirectional"))
      (node (ref "LEFT_MID2") (pin "A14") (pinfunction "A14_A14") (pintype "bidirectional"))
    )
    (net (code "73") (name "Net-(LEFT_MID1-PadA14)") (class "Default")
      (node (ref "LEFT_MID1") (pin "A14") (pinfunction "A14_A14") (pintype "bidirectional"))
      (node (ref "LEFT_MID2") (pin "B14") (pinfunction "B14_B14") (pintype "bidirectional"))
    )
    (net (code "74") (name "Net-(RIGHT_HP-PadA14)") (class "Default")
      (node (ref "RIGHT_HP") (pin "A14") (pinfunction "A14_A14") (pintype "bidirectional"))
      (node (ref "RIGHT_MID1") (pin "B14") (pinfunction "B14_B14") (pintype "bidirectional"))
    )
    (net (code "75") (name "Net-(RIGHT_LP-PadB14)") (class "Default")
      (node (ref "RIGHT_LP") (pin "B14") (pinfunction "B14_B14") (pintype "bidirectional"))
      (node (ref "RIGHT_MID2") (pin "A14") (pinfunction "A14_A14") (pintype "bidirectional"))
    )
    (net (code "76") (name "Net-(RIGHT_MID1-PadA14)") (class "Default")
      (node (ref "RIGHT_MID1") (pin "A14") (pinfunction "A14_A14") (pintype "bidirectional"))
      (node (ref "RIGHT_MID2") (pin "B14") (pinfunction "B14_B14") (pintype "bidirectional"))
    )
    (net (code "77") (name "R-IN") (class "Default")
      (node (ref "J2") (pin "1") (pinfunction "1_1") (pintype "bidirectional"))
      (node (ref "RIGHT_HP") (pin "B14") (pinfunction "B14_B14") (pintype "bidirectional"))
    )
    (net (code "78") (name "R-OUT") (class "Default")
      (node (ref "J2") (pin "2") (pinfunction "2_2") (pintype "bidirectional"))
      (node (ref "RIGHT_LP") (pin "A14") (pinfunction "A14_A14") (pintype "bidirectional"))
    )
    (net (code "79") (name "SPI1_MISO") (class "Default")
      (node (ref "IC6") (pin "12") (pinfunction "PA6_12") (pintype "bidirectional"))
    )
    (net (code "80") (name "SPI1_MOSI") (class "Default")
      (node (ref "IC6") (pin "13") (pinfunction "PA7_13") (pintype "bidirectional"))
      (node (ref "R56") (pin "2") (pinfunction "2_2") (pintype "passive"))
    )
    (net (code "81") (name "SPI1_SCK") (class "Default")
      (node (ref "IC6") (pin "11") (pinfunction "PA5_11") (pintype "bidirectional"))
      (node (ref "R62") (pin "2") (pinfunction "2_2") (pintype "passive"))
    )
    (net (code "82") (name "SWCLK") (class "Default")
      (node (ref "IC6") (pin "24") (pinfunction "PA14_24") (pintype "bidirectional"))
      (node (ref "PRG-CONN") (pin "1") (pinfunction "1_1") (pintype "bidirectional"))
    )
    (net (code "83") (name "SWDIO") (class "Default")
      (node (ref "IC6") (pin "23") (pinfunction "PA13_23") (pintype "bidirectional"))
      (node (ref "PRG-CONN") (pin "3") (pinfunction "3_3") (pintype "bidirectional"))
    )
    (net (code "84") (name "USART_RX") (class "Default")
      (node (ref "IC6") (pin "25") (pinfunction "PA15_25") (pintype "bidirectional"))
    )
    (net (code "85") (name "USART_TX") (class "Default")
      (node (ref "IC6") (pin "8") (pinfunction "PA2_8") (pintype "bidirectional"))
    )
    (net (code "86") (name "unconnected-(LEFT_HP-PadA1)") (class "Default")
      (node (ref "LEFT_HP") (pin "A1") (pinfunction "A1_A1") (pintype "bidirectional"))
    )
    (net (code "87") (name "unconnected-(LEFT_HP-PadA2)") (class "Default")
      (node (ref "LEFT_HP") (pin "A2") (pinfunction "A2_A2") (pintype "bidirectional"))
    )
    (net (code "88") (name "unconnected-(LEFT_HP-PadA3)") (class "Default")
      (node (ref "LEFT_HP") (pin "A3") (pinfunction "A3_A3") (pintype "bidirectional"))
    )
    (net (code "89") (name "unconnected-(LEFT_HP-PadA4)") (class "Default")
      (node (ref "LEFT_HP") (pin "A4") (pinfunction "A4_A4") (pintype "bidirectional"))
    )
    (net (code "90") (name "unconnected-(LEFT_HP-PadA5)") (class "Default")
      (node (ref "LEFT_HP") (pin "A5") (pinfunction "A5_A5") (pintype "bidirectional"))
    )
    (net (code "91") (name "unconnected-(LEFT_HP-PadA6)") (class "Default")
      (node (ref "LEFT_HP") (pin "A6") (pinfunction "A6_A6") (pintype "bidirectional"))
    )
    (net (code "92") (name "unconnected-(LEFT_HP-PadA7)") (class "Default")
      (node (ref "LEFT_HP") (pin "A7") (pinfunction "A7_A7") (pintype "bidirectional"))
    )
    (net (code "93") (name "unconnected-(LEFT_HP-PadA8)") (class "Default")
      (node (ref "LEFT_HP") (pin "A8") (pinfunction "A8_A8") (pintype "bidirectional"))
    )
    (net (code "94") (name "unconnected-(LEFT_HP-PadA9)") (class "Default")
      (node (ref "LEFT_HP") (pin "A9") (pinfunction "A9_A9") (pintype "bidirectional"))
    )
    (net (code "95") (name "unconnected-(LEFT_HP-PadA10)") (class "Default")
      (node (ref "LEFT_HP") (pin "A10") (pinfunction "A10_A10") (pintype "bidirectional"))
    )
    (net (code "96") (name "unconnected-(LEFT_HP-PadA11)") (class "Default")
      (node (ref "LEFT_HP") (pin "A11") (pinfunction "A11_A11") (pintype "bidirectional"))
    )
    (net (code "97") (name "unconnected-(LEFT_HP-PadA12)") (class "Default")
      (node (ref "LEFT_HP") (pin "A12") (pinfunction "A12_A12") (pintype "bidirectional"))
    )
    (net (code "98") (name "unconnected-(LEFT_HP-PadA13)") (class "Default")
      (node (ref "LEFT_HP") (pin "A13") (pinfunction "A13_A13") (pintype "bidirectional"))
    )
    (net (code "99") (name "unconnected-(LEFT_HP-PadA15)") (class "Default")
      (node (ref "LEFT_HP") (pin "A15") (pinfunction "A15_A15") (pintype "bidirectional"))
    )
    (net (code "100") (name "unconnected-(LEFT_HP-PadA16)") (class "Default")
      (node (ref "LEFT_HP") (pin "A16") (pinfunction "A16_A16") (pintype "bidirectional"))
    )
    (net (code "101") (name "unconnected-(LEFT_HP-PadB2)") (class "Default")
      (node (ref "LEFT_HP") (pin "B2") (pinfunction "B2_B2") (pintype "bidirectional"))
    )
    (net (code "102") (name "unconnected-(LEFT_HP-PadB3)") (class "Default")
      (node (ref "LEFT_HP") (pin "B3") (pinfunction "B3_B3") (pintype "bidirectional"))
    )
    (net (code "103") (name "unconnected-(LEFT_HP-PadB4)") (class "Default")
      (node (ref "LEFT_HP") (pin "B4") (pinfunction "B4_B4") (pintype "bidirectional"))
    )
    (net (code "104") (name "unconnected-(LEFT_HP-PadB5)") (class "Default")
      (node (ref "LEFT_HP") (pin "B5") (pinfunction "B5_B5") (pintype "bidirectional"))
    )
    (net (code "105") (name "unconnected-(LEFT_HP-PadB6)") (class "Default")
      (node (ref "LEFT_HP") (pin "B6") (pinfunction "B6_B6") (pintype "bidirectional"))
    )
    (net (code "106") (name "unconnected-(LEFT_HP-PadB12)") (class "Default")
      (node (ref "LEFT_HP") (pin "B12") (pinfunction "B12_B12") (pintype "bidirectional"))
    )
    (net (code "107") (name "unconnected-(LEFT_HP-PadB13)") (class "Default")
      (node (ref "LEFT_HP") (pin "B13") (pinfunction "B13_B13") (pintype "bidirectional"))
    )
    (net (code "108") (name "unconnected-(LEFT_HP-PadB15)") (class "Default")
      (node (ref "LEFT_HP") (pin "B15") (pinfunction "B15_B15") (pintype "bidirectional"))
    )
    (net (code "109") (name "unconnected-(LEFT_LP-PadA1)") (class "Default")
      (node (ref "LEFT_LP") (pin "A1") (pinfunction "A1_A1") (pintype "bidirectional"))
    )
    (net (code "110") (name "unconnected-(LEFT_LP-PadA2)") (class "Default")
      (node (ref "LEFT_LP") (pin "A2") (pinfunction "A2_A2") (pintype "bidirectional"))
    )
    (net (code "111") (name "unconnected-(LEFT_LP-PadA3)") (class "Default")
      (node (ref "LEFT_LP") (pin "A3") (pinfunction "A3_A3") (pintype "bidirectional"))
    )
    (net (code "112") (name "unconnected-(LEFT_LP-PadA4)") (class "Default")
      (node (ref "LEFT_LP") (pin "A4") (pinfunction "A4_A4") (pintype "bidirectional"))
    )
    (net (code "113") (name "unconnected-(LEFT_LP-PadA5)") (class "Default")
      (node (ref "LEFT_LP") (pin "A5") (pinfunction "A5_A5") (pintype "bidirectional"))
    )
    (net (code "114") (name "unconnected-(LEFT_LP-PadA6)") (class "Default")
      (node (ref "LEFT_LP") (pin "A6") (pinfunction "A6_A6") (pintype "bidirectional"))
    )
    (net (code "115") (name "unconnected-(LEFT_LP-PadA7)") (class "Default")
      (node (ref "LEFT_LP") (pin "A7") (pinfunction "A7_A7") (pintype "bidirectional"))
    )
    (net (code "116") (name "unconnected-(LEFT_LP-PadA8)") (class "Default")
      (node (ref "LEFT_LP") (pin "A8") (pinfunction "A8_A8") (pintype "bidirectional"))
    )
    (net (code "117") (name "unconnected-(LEFT_LP-PadA9)") (class "Default")
      (node (ref "LEFT_LP") (pin "A9") (pinfunction "A9_A9") (pintype "bidirectional"))
    )
    (net (code "118") (name "unconnected-(LEFT_LP-PadA10)") (class "Default")
      (node (ref "LEFT_LP") (pin "A10") (pinfunction "A10_A10") (pintype "bidirectional"))
    )
    (net (code "119") (name "unconnected-(LEFT_LP-PadA11)") (class "Default")
      (node (ref "LEFT_LP") (pin "A11") (pinfunction "A11_A11") (pintype "bidirectional"))
    )
    (net (code "120") (name "unconnected-(LEFT_LP-PadA12)") (class "Default")
      (node (ref "LEFT_LP") (pin "A12") (pinfunction "A12_A12") (pintype "bidirectional"))
    )
    (net (code "121") (name "unconnected-(LEFT_LP-PadA13)") (class "Default")
      (node (ref "LEFT_LP") (pin "A13") (pinfunction "A13_A13") (pintype "bidirectional"))
    )
    (net (code "122") (name "unconnected-(LEFT_LP-PadA15)") (class "Default")
      (node (ref "LEFT_LP") (pin "A15") (pinfunction "A15_A15") (pintype "bidirectional"))
    )
    (net (code "123") (name "unconnected-(LEFT_LP-PadA16)") (class "Default")
      (node (ref "LEFT_LP") (pin "A16") (pinfunction "A16_A16") (pintype "bidirectional"))
    )
    (net (code "124") (name "unconnected-(LEFT_LP-PadB2)") (class "Default")
      (node (ref "LEFT_LP") (pin "B2") (pinfunction "B2_B2") (pintype "bidirectional"))
    )
    (net (code "125") (name "unconnected-(LEFT_LP-PadB3)") (class "Default")
      (node (ref "LEFT_LP") (pin "B3") (pinfunction "B3_B3") (pintype "bidirectional"))
    )
    (net (code "126") (name "unconnected-(LEFT_LP-PadB4)") (class "Default")
      (node (ref "LEFT_LP") (pin "B4") (pinfunction "B4_B4") (pintype "bidirectional"))
    )
    (net (code "127") (name "unconnected-(LEFT_LP-PadB5)") (class "Default")
      (node (ref "LEFT_LP") (pin "B5") (pinfunction "B5_B5") (pintype "bidirectional"))
    )
    (net (code "128") (name "unconnected-(LEFT_LP-PadB6)") (class "Default")
      (node (ref "LEFT_LP") (pin "B6") (pinfunction "B6_B6") (pintype "bidirectional"))
    )
    (net (code "129") (name "unconnected-(LEFT_LP-PadB12)") (class "Default")
      (node (ref "LEFT_LP") (pin "B12") (pinfunction "B12_B12") (pintype "bidirectional"))
    )
    (net (code "130") (name "unconnected-(LEFT_LP-PadB13)") (class "Default")
      (node (ref "LEFT_LP") (pin "B13") (pinfunction "B13_B13") (pintype "bidirectional"))
    )
    (net (code "131") (name "unconnected-(LEFT_LP-PadB15)") (class "Default")
      (node (ref "LEFT_LP") (pin "B15") (pinfunction "B15_B15") (pintype "bidirectional"))
    )
    (net (code "132") (name "unconnected-(LEFT_MID1-PadA1)") (class "Default")
      (node (ref "LEFT_MID1") (pin "A1") (pinfunction "A1_A1") (pintype "bidirectional"))
    )
    (net (code "133") (name "unconnected-(LEFT_MID1-PadA2)") (class "Default")
      (node (ref "LEFT_MID1") (pin "A2") (pinfunction "A2_A2") (pintype "bidirectional"))
    )
    (net (code "134") (name "unconnected-(LEFT_MID1-PadA3)") (class "Default")
      (node (ref "LEFT_MID1") (pin "A3") (pinfunction "A3_A3") (pintype "bidirectional"))
    )
    (net (code "135") (name "unconnected-(LEFT_MID1-PadA4)") (class "Default")
      (node (ref "LEFT_MID1") (pin "A4") (pinfunction "A4_A4") (pintype "bidirectional"))
    )
    (net (code "136") (name "unconnected-(LEFT_MID1-PadA5)") (class "Default")
      (node (ref "LEFT_MID1") (pin "A5") (pinfunction "A5_A5") (pintype "bidirectional"))
    )
    (net (code "137") (name "unconnected-(LEFT_MID1-PadA6)") (class "Default")
      (node (ref "LEFT_MID1") (pin "A6") (pinfunction "A6_A6") (pintype "bidirectional"))
    )
    (net (code "138") (name "unconnected-(LEFT_MID1-PadA7)") (class "Default")
      (node (ref "LEFT_MID1") (pin "A7") (pinfunction "A7_A7") (pintype "bidirectional"))
    )
    (net (code "139") (name "unconnected-(LEFT_MID1-PadA8)") (class "Default")
      (node (ref "LEFT_MID1") (pin "A8") (pinfunction "A8_A8") (pintype "bidirectional"))
    )
    (net (code "140") (name "unconnected-(LEFT_MID1-PadA9)") (class "Default")
      (node (ref "LEFT_MID1") (pin "A9") (pinfunction "A9_A9") (pintype "bidirectional"))
    )
    (net (code "141") (name "unconnected-(LEFT_MID1-PadA10)") (class "Default")
      (node (ref "LEFT_MID1") (pin "A10") (pinfunction "A10_A10") (pintype "bidirectional"))
    )
    (net (code "142") (name "unconnected-(LEFT_MID1-PadA11)") (class "Default")
      (node (ref "LEFT_MID1") (pin "A11") (pinfunction "A11_A11") (pintype "bidirectional"))
    )
    (net (code "143") (name "unconnected-(LEFT_MID1-PadA12)") (class "Default")
      (node (ref "LEFT_MID1") (pin "A12") (pinfunction "A12_A12") (pintype "bidirectional"))
    )
    (net (code "144") (name "unconnected-(LEFT_MID1-PadA13)") (class "Default")
      (node (ref "LEFT_MID1") (pin "A13") (pinfunction "A13_A13") (pintype "bidirectional"))
    )
    (net (code "145") (name "unconnected-(LEFT_MID1-PadA15)") (class "Default")
      (node (ref "LEFT_MID1") (pin "A15") (pinfunction "A15_A15") (pintype "bidirectional"))
    )
    (net (code "146") (name "unconnected-(LEFT_MID1-PadA16)") (class "Default")
      (node (ref "LEFT_MID1") (pin "A16") (pinfunction "A16_A16") (pintype "bidirectional"))
    )
    (net (code "147") (name "unconnected-(LEFT_MID1-PadB2)") (class "Default")
      (node (ref "LEFT_MID1") (pin "B2") (pinfunction "B2_B2") (pintype "bidirectional"))
    )
    (net (code "148") (name "unconnected-(LEFT_MID1-PadB3)") (class "Default")
      (node (ref "LEFT_MID1") (pin "B3") (pinfunction "B3_B3") (pintype "bidirectional"))
    )
    (net (code "149") (name "unconnected-(LEFT_MID1-PadB4)") (class "Default")
      (node (ref "LEFT_MID1") (pin "B4") (pinfunction "B4_B4") (pintype "bidirectional"))
    )
    (net (code "150") (name "unconnected-(LEFT_MID1-PadB5)") (class "Default")
      (node (ref "LEFT_MID1") (pin "B5") (pinfunction "B5_B5") (pintype "bidirectional"))
    )
    (net (code "151") (name "unconnected-(LEFT_MID1-PadB6)") (class "Default")
      (node (ref "LEFT_MID1") (pin "B6") (pinfunction "B6_B6") (pintype "bidirectional"))
    )
    (net (code "152") (name "unconnected-(LEFT_MID1-PadB12)") (class "Default")
      (node (ref "LEFT_MID1") (pin "B12") (pinfunction "B12_B12") (pintype "bidirectional"))
    )
    (net (code "153") (name "unconnected-(LEFT_MID1-PadB13)") (class "Default")
      (node (ref "LEFT_MID1") (pin "B13") (pinfunction "B13_B13") (pintype "bidirectional"))
    )
    (net (code "154") (name "unconnected-(LEFT_MID1-PadB15)") (class "Default")
      (node (ref "LEFT_MID1") (pin "B15") (pinfunction "B15_B15") (pintype "bidirectional"))
    )
    (net (code "155") (name "unconnected-(LEFT_MID2-PadA1)") (class "Default")
      (node (ref "LEFT_MID2") (pin "A1") (pinfunction "A1_A1") (pintype "bidirectional"))
    )
    (net (code "156") (name "unconnected-(LEFT_MID2-PadA2)") (class "Default")
      (node (ref "LEFT_MID2") (pin "A2") (pinfunction "A2_A2") (pintype "bidirectional"))
    )
    (net (code "157") (name "unconnected-(LEFT_MID2-PadA3)") (class "Default")
      (node (ref "LEFT_MID2") (pin "A3") (pinfunction "A3_A3") (pintype "bidirectional"))
    )
    (net (code "158") (name "unconnected-(LEFT_MID2-PadA4)") (class "Default")
      (node (ref "LEFT_MID2") (pin "A4") (pinfunction "A4_A4") (pintype "bidirectional"))
    )
    (net (code "159") (name "unconnected-(LEFT_MID2-PadA5)") (class "Default")
      (node (ref "LEFT_MID2") (pin "A5") (pinfunction "A5_A5") (pintype "bidirectional"))
    )
    (net (code "160") (name "unconnected-(LEFT_MID2-PadA6)") (class "Default")
      (node (ref "LEFT_MID2") (pin "A6") (pinfunction "A6_A6") (pintype "bidirectional"))
    )
    (net (code "161") (name "unconnected-(LEFT_MID2-PadA7)") (class "Default")
      (node (ref "LEFT_MID2") (pin "A7") (pinfunction "A7_A7") (pintype "bidirectional"))
    )
    (net (code "162") (name "unconnected-(LEFT_MID2-PadA8)") (class "Default")
      (node (ref "LEFT_MID2") (pin "A8") (pinfunction "A8_A8") (pintype "bidirectional"))
    )
    (net (code "163") (name "unconnected-(LEFT_MID2-PadA9)") (class "Default")
      (node (ref "LEFT_MID2") (pin "A9") (pinfunction "A9_A9") (pintype "bidirectional"))
    )
    (net (code "164") (name "unconnected-(LEFT_MID2-PadA10)") (class "Default")
      (node (ref "LEFT_MID2") (pin "A10") (pinfunction "A10_A10") (pintype "bidirectional"))
    )
    (net (code "165") (name "unconnected-(LEFT_MID2-PadA11)") (class "Default")
      (node (ref "LEFT_MID2") (pin "A11") (pinfunction "A11_A11") (pintype "bidirectional"))
    )
    (net (code "166") (name "unconnected-(LEFT_MID2-PadA12)") (class "Default")
      (node (ref "LEFT_MID2") (pin "A12") (pinfunction "A12_A12") (pintype "bidirectional"))
    )
    (net (code "167") (name "unconnected-(LEFT_MID2-PadA13)") (class "Default")
      (node (ref "LEFT_MID2") (pin "A13") (pinfunction "A13_A13") (pintype "bidirectional"))
    )
    (net (code "168") (name "unconnected-(LEFT_MID2-PadA15)") (class "Default")
      (node (ref "LEFT_MID2") (pin "A15") (pinfunction "A15_A15") (pintype "bidirectional"))
    )
    (net (code "169") (name "unconnected-(LEFT_MID2-PadA16)") (class "Default")
      (node (ref "LEFT_MID2") (pin "A16") (pinfunction "A16_A16") (pintype "bidirectional"))
    )
    (net (code "170") (name "unconnected-(LEFT_MID2-PadB2)") (class "Default")
      (node (ref "LEFT_MID2") (pin "B2") (pinfunction "B2_B2") (pintype "bidirectional"))
    )
    (net (code "171") (name "unconnected-(LEFT_MID2-PadB3)") (class "Default")
      (node (ref "LEFT_MID2") (pin "B3") (pinfunction "B3_B3") (pintype "bidirectional"))
    )
    (net (code "172") (name "unconnected-(LEFT_MID2-PadB4)") (class "Default")
      (node (ref "LEFT_MID2") (pin "B4") (pinfunction "B4_B4") (pintype "bidirectional"))
    )
    (net (code "173") (name "unconnected-(LEFT_MID2-PadB5)") (class "Default")
      (node (ref "LEFT_MID2") (pin "B5") (pinfunction "B5_B5") (pintype "bidirectional"))
    )
    (net (code "174") (name "unconnected-(LEFT_MID2-PadB6)") (class "Default")
      (node (ref "LEFT_MID2") (pin "B6") (pinfunction "B6_B6") (pintype "bidirectional"))
    )
    (net (code "175") (name "unconnected-(LEFT_MID2-PadB12)") (class "Default")
      (node (ref "LEFT_MID2") (pin "B12") (pinfunction "B12_B12") (pintype "bidirectional"))
    )
    (net (code "176") (name "unconnected-(LEFT_MID2-PadB13)") (class "Default")
      (node (ref "LEFT_MID2") (pin "B13") (pinfunction "B13_B13") (pintype "bidirectional"))
    )
    (net (code "177") (name "unconnected-(LEFT_MID2-PadB15)") (class "Default")
      (node (ref "LEFT_MID2") (pin "B15") (pinfunction "B15_B15") (pintype "bidirectional"))
    )
    (net (code "178") (name "unconnected-(RIGHT_HP-PadA1)") (class "Default")
      (node (ref "RIGHT_HP") (pin "A1") (pinfunction "A1_A1") (pintype "bidirectional"))
    )
    (net (code "179") (name "unconnected-(RIGHT_HP-PadA2)") (class "Default")
      (node (ref "RIGHT_HP") (pin "A2") (pinfunction "A2_A2") (pintype "bidirectional"))
    )
    (net (code "180") (name "unconnected-(RIGHT_HP-PadA3)") (class "Default")
      (node (ref "RIGHT_HP") (pin "A3") (pinfunction "A3_A3") (pintype "bidirectional"))
    )
    (net (code "181") (name "unconnected-(RIGHT_HP-PadA4)") (class "Default")
      (node (ref "RIGHT_HP") (pin "A4") (pinfunction "A4_A4") (pintype "bidirectional"))
    )
    (net (code "182") (name "unconnected-(RIGHT_HP-PadA5)") (class "Default")
      (node (ref "RIGHT_HP") (pin "A5") (pinfunction "A5_A5") (pintype "bidirectional"))
    )
    (net (code "183") (name "unconnected-(RIGHT_HP-PadA6)") (class "Default")
      (node (ref "RIGHT_HP") (pin "A6") (pinfunction "A6_A6") (pintype "bidirectional"))
    )
    (net (code "184") (name "unconnected-(RIGHT_HP-PadA7)") (class "Default")
      (node (ref "RIGHT_HP") (pin "A7") (pinfunction "A7_A7") (pintype "bidirectional"))
    )
    (net (code "185") (name "unconnected-(RIGHT_HP-PadA8)") (class "Default")
      (node (ref "RIGHT_HP") (pin "A8") (pinfunction "A8_A8") (pintype "bidirectional"))
    )
    (net (code "186") (name "unconnected-(RIGHT_HP-PadA9)") (class "Default")
      (node (ref "RIGHT_HP") (pin "A9") (pinfunction "A9_A9") (pintype "bidirectional"))
    )
    (net (code "187") (name "unconnected-(RIGHT_HP-PadA10)") (class "Default")
      (node (ref "RIGHT_HP") (pin "A10") (pinfunction "A10_A10") (pintype "bidirectional"))
    )
    (net (code "188") (name "unconnected-(RIGHT_HP-PadA11)") (class "Default")
      (node (ref "RIGHT_HP") (pin "A11") (pinfunction "A11_A11") (pintype "bidirectional"))
    )
    (net (code "189") (name "unconnected-(RIGHT_HP-PadA12)") (class "Default")
      (node (ref "RIGHT_HP") (pin "A12") (pinfunction "A12_A12") (pintype "bidirectional"))
    )
    (net (code "190") (name "unconnected-(RIGHT_HP-PadA13)") (class "Default")
      (node (ref "RIGHT_HP") (pin "A13") (pinfunction "A13_A13") (pintype "bidirectional"))
    )
    (net (code "191") (name "unconnected-(RIGHT_HP-PadA15)") (class "Default")
      (node (ref "RIGHT_HP") (pin "A15") (pinfunction "A15_A15") (pintype "bidirectional"))
    )
    (net (code "192") (name "unconnected-(RIGHT_HP-PadA16)") (class "Default")
      (node (ref "RIGHT_HP") (pin "A16") (pinfunction "A16_A16") (pintype "bidirectional"))
    )
    (net (code "193") (name "unconnected-(RIGHT_HP-PadB2)") (class "Default")
      (node (ref "RIGHT_HP") (pin "B2") (pinfunction "B2_B2") (pintype "bidirectional"))
    )
    (net (code "194") (name "unconnected-(RIGHT_HP-PadB3)") (class "Default")
      (node (ref "RIGHT_HP") (pin "B3") (pinfunction "B3_B3") (pintype "bidirectional"))
    )
    (net (code "195") (name "unconnected-(RIGHT_HP-PadB4)") (class "Default")
      (node (ref "RIGHT_HP") (pin "B4") (pinfunction "B4_B4") (pintype "bidirectional"))
    )
    (net (code "196") (name "unconnected-(RIGHT_HP-PadB5)") (class "Default")
      (node (ref "RIGHT_HP") (pin "B5") (pinfunction "B5_B5") (pintype "bidirectional"))
    )
    (net (code "197") (name "unconnected-(RIGHT_HP-PadB6)") (class "Default")
      (node (ref "RIGHT_HP") (pin "B6") (pinfunction "B6_B6") (pintype "bidirectional"))
    )
    (net (code "198") (name "unconnected-(RIGHT_HP-PadB12)") (class "Default")
      (node (ref "RIGHT_HP") (pin "B12") (pinfunction "B12_B12") (pintype "bidirectional"))
    )
    (net (code "199") (name "unconnected-(RIGHT_HP-PadB13)") (class "Default")
      (node (ref "RIGHT_HP") (pin "B13") (pinfunction "B13_B13") (pintype "bidirectional"))
    )
    (net (code "200") (name "unconnected-(RIGHT_HP-PadB15)") (class "Default")
      (node (ref "RIGHT_HP") (pin "B15") (pinfunction "B15_B15") (pintype "bidirectional"))
    )
    (net (code "201") (name "unconnected-(RIGHT_LP-PadA1)") (class "Default")
      (node (ref "RIGHT_LP") (pin "A1") (pinfunction "A1_A1") (pintype "bidirectional"))
    )
    (net (code "202") (name "unconnected-(RIGHT_LP-PadA2)") (class "Default")
      (node (ref "RIGHT_LP") (pin "A2") (pinfunction "A2_A2") (pintype "bidirectional"))
    )
    (net (code "203") (name "unconnected-(RIGHT_LP-PadA3)") (class "Default")
      (node (ref "RIGHT_LP") (pin "A3") (pinfunction "A3_A3") (pintype "bidirectional"))
    )
    (net (code "204") (name "unconnected-(RIGHT_LP-PadA4)") (class "Default")
      (node (ref "RIGHT_LP") (pin "A4") (pinfunction "A4_A4") (pintype "bidirectional"))
    )
    (net (code "205") (name "unconnected-(RIGHT_LP-PadA5)") (class "Default")
      (node (ref "RIGHT_LP") (pin "A5") (pinfunction "A5_A5") (pintype "bidirectional"))
    )
    (net (code "206") (name "unconnected-(RIGHT_LP-PadA6)") (class "Default")
      (node (ref "RIGHT_LP") (pin "A6") (pinfunction "A6_A6") (pintype "bidirectional"))
    )
    (net (code "207") (name "unconnected-(RIGHT_LP-PadA7)") (class "Default")
      (node (ref "RIGHT_LP") (pin "A7") (pinfunction "A7_A7") (pintype "bidirectional"))
    )
    (net (code "208") (name "unconnected-(RIGHT_LP-PadA8)") (class "Default")
      (node (ref "RIGHT_LP") (pin "A8") (pinfunction "A8_A8") (pintype "bidirectional"))
    )
    (net (code "209") (name "unconnected-(RIGHT_LP-PadA9)") (class "Default")
      (node (ref "RIGHT_LP") (pin "A9") (pinfunction "A9_A9") (pintype "bidirectional"))
    )
    (net (code "210") (name "unconnected-(RIGHT_LP-PadA10)") (class "Default")
      (node (ref "RIGHT_LP") (pin "A10") (pinfunction "A10_A10") (pintype "bidirectional"))
    )
    (net (code "211") (name "unconnected-(RIGHT_LP-PadA11)") (class "Default")
      (node (ref "RIGHT_LP") (pin "A11") (pinfunction "A11_A11") (pintype "bidirectional"))
    )
    (net (code "212") (name "unconnected-(RIGHT_LP-PadA12)") (class "Default")
      (node (ref "RIGHT_LP") (pin "A12") (pinfunction "A12_A12") (pintype "bidirectional"))
    )
    (net (code "213") (name "unconnected-(RIGHT_LP-PadA13)") (class "Default")
      (node (ref "RIGHT_LP") (pin "A13") (pinfunction "A13_A13") (pintype "bidirectional"))
    )
    (net (code "214") (name "unconnected-(RIGHT_LP-PadA15)") (class "Default")
      (node (ref "RIGHT_LP") (pin "A15") (pinfunction "A15_A15") (pintype "bidirectional"))
    )
    (net (code "215") (name "unconnected-(RIGHT_LP-PadA16)") (class "Default")
      (node (ref "RIGHT_LP") (pin "A16") (pinfunction "A16_A16") (pintype "bidirectional"))
    )
    (net (code "216") (name "unconnected-(RIGHT_LP-PadB2)") (class "Default")
      (node (ref "RIGHT_LP") (pin "B2") (pinfunction "B2_B2") (pintype "bidirectional"))
    )
    (net (code "217") (name "unconnected-(RIGHT_LP-PadB3)") (class "Default")
      (node (ref "RIGHT_LP") (pin "B3") (pinfunction "B3_B3") (pintype "bidirectional"))
    )
    (net (code "218") (name "unconnected-(RIGHT_LP-PadB4)") (class "Default")
      (node (ref "RIGHT_LP") (pin "B4") (pinfunction "B4_B4") (pintype "bidirectional"))
    )
    (net (code "219") (name "unconnected-(RIGHT_LP-PadB5)") (class "Default")
      (node (ref "RIGHT_LP") (pin "B5") (pinfunction "B5_B5") (pintype "bidirectional"))
    )
    (net (code "220") (name "unconnected-(RIGHT_LP-PadB6)") (class "Default")
      (node (ref "RIGHT_LP") (pin "B6") (pinfunction "B6_B6") (pintype "bidirectional"))
    )
    (net (code "221") (name "unconnected-(RIGHT_LP-PadB12)") (class "Default")
      (node (ref "RIGHT_LP") (pin "B12") (pinfunction "B12_B12") (pintype "bidirectional"))
    )
    (net (code "222") (name "unconnected-(RIGHT_LP-PadB13)") (class "Default")
      (node (ref "RIGHT_LP") (pin "B13") (pinfunction "B13_B13") (pintype "bidirectional"))
    )
    (net (code "223") (name "unconnected-(RIGHT_LP-PadB15)") (class "Default")
      (node (ref "RIGHT_LP") (pin "B15") (pinfunction "B15_B15") (pintype "bidirectional"))
    )
    (net (code "224") (name "unconnected-(RIGHT_MID1-PadA1)") (class "Default")
      (node (ref "RIGHT_MID1") (pin "A1") (pinfunction "A1_A1") (pintype "bidirectional"))
    )
    (net (code "225") (name "unconnected-(RIGHT_MID1-PadA2)") (class "Default")
      (node (ref "RIGHT_MID1") (pin "A2") (pinfunction "A2_A2") (pintype "bidirectional"))
    )
    (net (code "226") (name "unconnected-(RIGHT_MID1-PadA3)") (class "Default")
      (node (ref "RIGHT_MID1") (pin "A3") (pinfunction "A3_A3") (pintype "bidirectional"))
    )
    (net (code "227") (name "unconnected-(RIGHT_MID1-PadA4)") (class "Default")
      (node (ref "RIGHT_MID1") (pin "A4") (pinfunction "A4_A4") (pintype "bidirectional"))
    )
    (net (code "228") (name "unconnected-(RIGHT_MID1-PadA5)") (class "Default")
      (node (ref "RIGHT_MID1") (pin "A5") (pinfunction "A5_A5") (pintype "bidirectional"))
    )
    (net (code "229") (name "unconnected-(RIGHT_MID1-PadA6)") (class "Default")
      (node (ref "RIGHT_MID1") (pin "A6") (pinfunction "A6_A6") (pintype "bidirectional"))
    )
    (net (code "230") (name "unconnected-(RIGHT_MID1-PadA7)") (class "Default")
      (node (ref "RIGHT_MID1") (pin "A7") (pinfunction "A7_A7") (pintype "bidirectional"))
    )
    (net (code "231") (name "unconnected-(RIGHT_MID1-PadA8)") (class "Default")
      (node (ref "RIGHT_MID1") (pin "A8") (pinfunction "A8_A8") (pintype "bidirectional"))
    )
    (net (code "232") (name "unconnected-(RIGHT_MID1-PadA9)") (class "Default")
      (node (ref "RIGHT_MID1") (pin "A9") (pinfunction "A9_A9") (pintype "bidirectional"))
    )
    (net (code "233") (name "unconnected-(RIGHT_MID1-PadA10)") (class "Default")
      (node (ref "RIGHT_MID1") (pin "A10") (pinfunction "A10_A10") (pintype "bidirectional"))
    )
    (net (code "234") (name "unconnected-(RIGHT_MID1-PadA11)") (class "Default")
      (node (ref "RIGHT_MID1") (pin "A11") (pinfunction "A11_A11") (pintype "bidirectional"))
    )
    (net (code "235") (name "unconnected-(RIGHT_MID1-PadA12)") (class "Default")
      (node (ref "RIGHT_MID1") (pin "A12") (pinfunction "A12_A12") (pintype "bidirectional"))
    )
    (net (code "236") (name "unconnected-(RIGHT_MID1-PadA13)") (class "Default")
      (node (ref "RIGHT_MID1") (pin "A13") (pinfunction "A13_A13") (pintype "bidirectional"))
    )
    (net (code "237") (name "unconnected-(RIGHT_MID1-PadA15)") (class "Default")
      (node (ref "RIGHT_MID1") (pin "A15") (pinfunction "A15_A15") (pintype "bidirectional"))
    )
    (net (code "238") (name "unconnected-(RIGHT_MID1-PadA16)") (class "Default")
      (node (ref "RIGHT_MID1") (pin "A16") (pinfunction "A16_A16") (pintype "bidirectional"))
    )
    (net (code "239") (name "unconnected-(RIGHT_MID1-PadB2)") (class "Default")
      (node (ref "RIGHT_MID1") (pin "B2") (pinfunction "B2_B2") (pintype "bidirectional"))
    )
    (net (code "240") (name "unconnected-(RIGHT_MID1-PadB3)") (class "Default")
      (node (ref "RIGHT_MID1") (pin "B3") (pinfunction "B3_B3") (pintype "bidirectional"))
    )
    (net (code "241") (name "unconnected-(RIGHT_MID1-PadB4)") (class "Default")
      (node (ref "RIGHT_MID1") (pin "B4") (pinfunction "B4_B4") (pintype "bidirectional"))
    )
    (net (code "242") (name "unconnected-(RIGHT_MID1-PadB5)") (class "Default")
      (node (ref "RIGHT_MID1") (pin "B5") (pinfunction "B5_B5") (pintype "bidirectional"))
    )
    (net (code "243") (name "unconnected-(RIGHT_MID1-PadB6)") (class "Default")
      (node (ref "RIGHT_MID1") (pin "B6") (pinfunction "B6_B6") (pintype "bidirectional"))
    )
    (net (code "244") (name "unconnected-(RIGHT_MID1-PadB12)") (class "Default")
      (node (ref "RIGHT_MID1") (pin "B12") (pinfunction "B12_B12") (pintype "bidirectional"))
    )
    (net (code "245") (name "unconnected-(RIGHT_MID1-PadB13)") (class "Default")
      (node (ref "RIGHT_MID1") (pin "B13") (pinfunction "B13_B13") (pintype "bidirectional"))
    )
    (net (code "246") (name "unconnected-(RIGHT_MID1-PadB15)") (class "Default")
      (node (ref "RIGHT_MID1") (pin "B15") (pinfunction "B15_B15") (pintype "bidirectional"))
    )
    (net (code "247") (name "unconnected-(RIGHT_MID2-PadA1)") (class "Default")
      (node (ref "RIGHT_MID2") (pin "A1") (pinfunction "A1_A1") (pintype "bidirectional"))
    )
    (net (code "248") (name "unconnected-(RIGHT_MID2-PadA2)") (class "Default")
      (node (ref "RIGHT_MID2") (pin "A2") (pinfunction "A2_A2") (pintype "bidirectional"))
    )
    (net (code "249") (name "unconnected-(RIGHT_MID2-PadA3)") (class "Default")
      (node (ref "RIGHT_MID2") (pin "A3") (pinfunction "A3_A3") (pintype "bidirectional"))
    )
    (net (code "250") (name "unconnected-(RIGHT_MID2-PadA4)") (class "Default")
      (node (ref "RIGHT_MID2") (pin "A4") (pinfunction "A4_A4") (pintype "bidirectional"))
    )
    (net (code "251") (name "unconnected-(RIGHT_MID2-PadA5)") (class "Default")
      (node (ref "RIGHT_MID2") (pin "A5") (pinfunction "A5_A5") (pintype "bidirectional"))
    )
    (net (code "252") (name "unconnected-(RIGHT_MID2-PadA6)") (class "Default")
      (node (ref "RIGHT_MID2") (pin "A6") (pinfunction "A6_A6") (pintype "bidirectional"))
    )
    (net (code "253") (name "unconnected-(RIGHT_MID2-PadA7)") (class "Default")
      (node (ref "RIGHT_MID2") (pin "A7") (pinfunction "A7_A7") (pintype "bidirectional"))
    )
    (net (code "254") (name "unconnected-(RIGHT_MID2-PadA8)") (class "Default")
      (node (ref "RIGHT_MID2") (pin "A8") (pinfunction "A8_A8") (pintype "bidirectional"))
    )
    (net (code "255") (name "unconnected-(RIGHT_MID2-PadA9)") (class "Default")
      (node (ref "RIGHT_MID2") (pin "A9") (pinfunction "A9_A9") (pintype "bidirectional"))
    )
    (net (code "256") (name "unconnected-(RIGHT_MID2-PadA10)") (class "Default")
      (node (ref "RIGHT_MID2") (pin "A10") (pinfunction "A10_A10") (pintype "bidirectional"))
    )
    (net (code "257") (name "unconnected-(RIGHT_MID2-PadA11)") (class "Default")
      (node (ref "RIGHT_MID2") (pin "A11") (pinfunction "A11_A11") (pintype "bidirectional"))
    )
    (net (code "258") (name "unconnected-(RIGHT_MID2-PadA12)") (class "Default")
      (node (ref "RIGHT_MID2") (pin "A12") (pinfunction "A12_A12") (pintype "bidirectional"))
    )
    (net (code "259") (name "unconnected-(RIGHT_MID2-PadA13)") (class "Default")
      (node (ref "RIGHT_MID2") (pin "A13") (pinfunction "A13_A13") (pintype "bidirectional"))
    )
    (net (code "260") (name "unconnected-(RIGHT_MID2-PadA15)") (class "Default")
      (node (ref "RIGHT_MID2") (pin "A15") (pinfunction "A15_A15") (pintype "bidirectional"))
    )
    (net (code "261") (name "unconnected-(RIGHT_MID2-PadA16)") (class "Default")
      (node (ref "RIGHT_MID2") (pin "A16") (pinfunction "A16_A16") (pintype "bidirectional"))
    )
    (net (code "262") (name "unconnected-(RIGHT_MID2-PadB2)") (class "Default")
      (node (ref "RIGHT_MID2") (pin "B2") (pinfunction "B2_B2") (pintype "bidirectional"))
    )
    (net (code "263") (name "unconnected-(RIGHT_MID2-PadB3)") (class "Default")
      (node (ref "RIGHT_MID2") (pin "B3") (pinfunction "B3_B3") (pintype "bidirectional"))
    )
    (net (code "264") (name "unconnected-(RIGHT_MID2-PadB4)") (class "Default")
      (node (ref "RIGHT_MID2") (pin "B4") (pinfunction "B4_B4") (pintype "bidirectional"))
    )
    (net (code "265") (name "unconnected-(RIGHT_MID2-PadB5)") (class "Default")
      (node (ref "RIGHT_MID2") (pin "B5") (pinfunction "B5_B5") (pintype "bidirectional"))
    )
    (net (code "266") (name "unconnected-(RIGHT_MID2-PadB6)") (class "Default")
      (node (ref "RIGHT_MID2") (pin "B6") (pinfunction "B6_B6") (pintype "bidirectional"))
    )
    (net (code "267") (name "unconnected-(RIGHT_MID2-PadB12)") (class "Default")
      (node (ref "RIGHT_MID2") (pin "B12") (pinfunction "B12_B12") (pintype "bidirectional"))
    )
    (net (code "268") (name "unconnected-(RIGHT_MID2-PadB13)") (class "Default")
      (node (ref "RIGHT_MID2") (pin "B13") (pinfunction "B13_B13") (pintype "bidirectional"))
    )
    (net (code "269") (name "unconnected-(RIGHT_MID2-PadB15)") (class "Default")
      (node (ref "RIGHT_MID2") (pin "B15") (pinfunction "B15_B15") (pintype "bidirectional"))
    )
  )
)
